# MOSFETadded.net
KiCad netlist of a schematic drawn in EAGLE
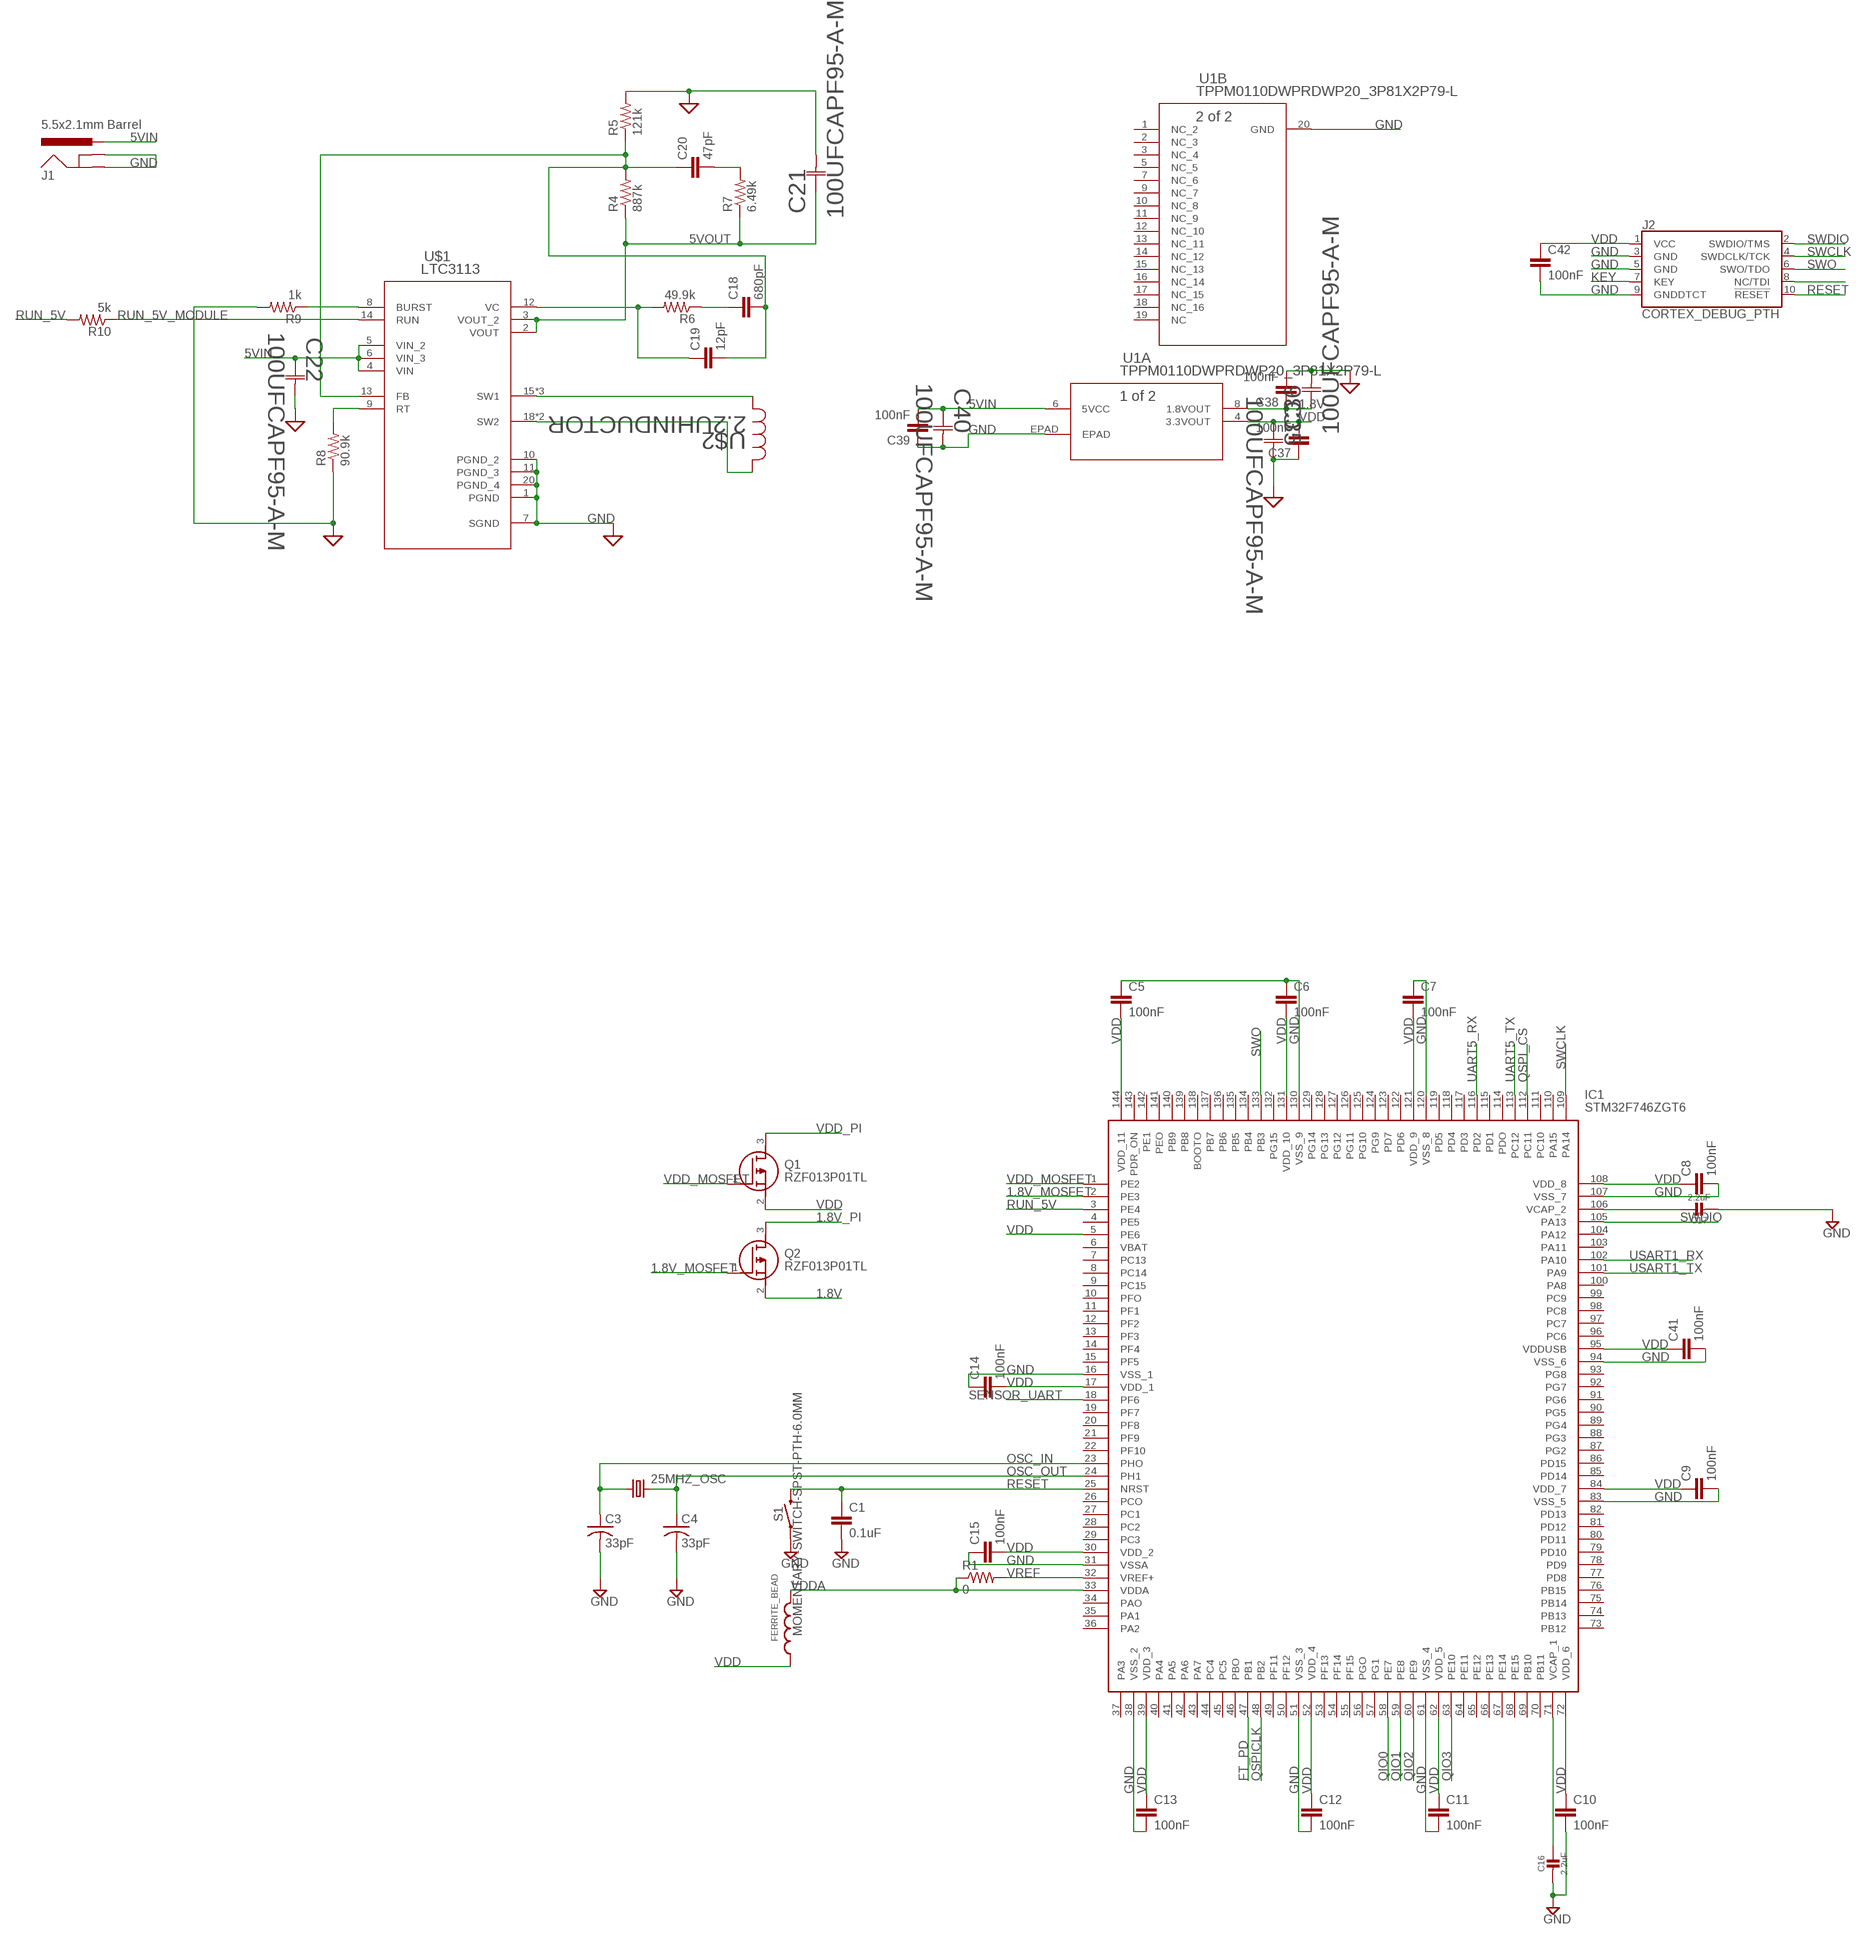
[diagram p0: schematic, sheet 1, part 1 of 2]
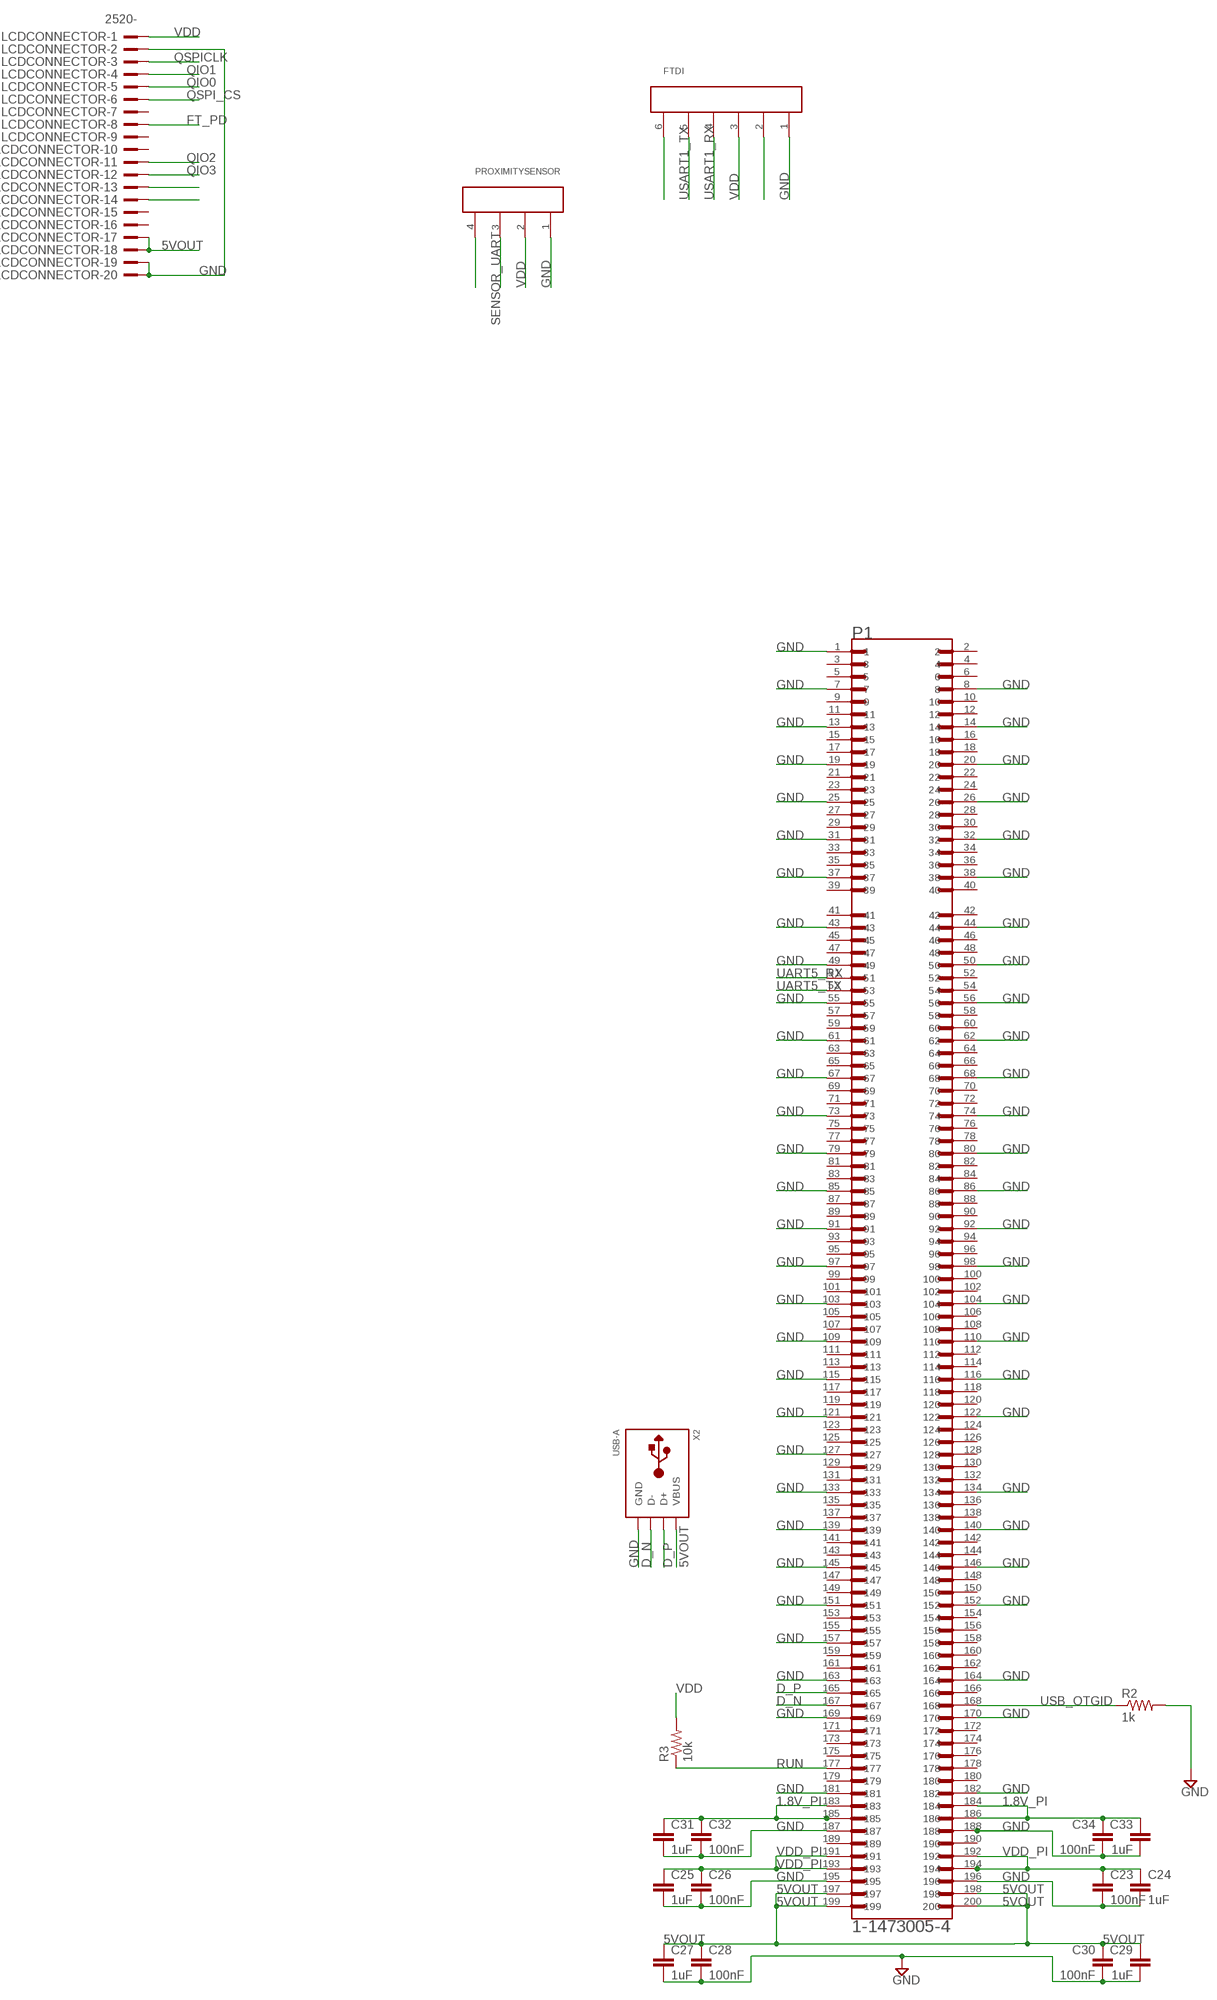
[diagram p1: schematic, sheet 1, part 2 of 2]

(export (version "E")
  (design (tool "Eeschema 10.0.6"))
  (components
    (comp (ref "25MHZ_OSC")
      (value "CRYSTALHC49UP")
      (footprint "eagle-import:HC49UP")
      (libsource (lib "eagle-import") (part "CRYSTALHC49UP"))
    )
    (comp (ref "C1")
      (value "0.1uF")
      (footprint "eagle-import:C0805")
      (libsource (lib "eagle-import") (part "C-EUC0805"))
    )
    (comp (ref "C3")
      (value "33pF")
      (footprint "eagle-import:C0805")
      (libsource (lib "eagle-import") (part "C-USC0805"))
    )
    (comp (ref "C4")
      (value "33pF")
      (footprint "eagle-import:C0805")
      (libsource (lib "eagle-import") (part "C-USC0805"))
    )
    (comp (ref "C5")
      (value "100nF")
      (footprint "eagle-import:C0805")
      (libsource (lib "eagle-import") (part "C-EUC0805"))
    )
    (comp (ref "C6")
      (value "100nF")
      (footprint "eagle-import:C0805")
      (libsource (lib "eagle-import") (part "C-EUC0805"))
    )
    (comp (ref "C7")
      (value "100nF")
      (footprint "eagle-import:C0805")
      (libsource (lib "eagle-import") (part "C-EUC0805"))
    )
    (comp (ref "C8")
      (value "100nF")
      (footprint "eagle-import:C0805")
      (libsource (lib "eagle-import") (part "C-EUC0805"))
    )
    (comp (ref "C9")
      (value "100nF")
      (footprint "eagle-import:C0805")
      (libsource (lib "eagle-import") (part "C-EUC0805"))
    )
    (comp (ref "C10")
      (value "100nF")
      (footprint "eagle-import:C0805")
      (libsource (lib "eagle-import") (part "C-EUC0805"))
    )
    (comp (ref "C11")
      (value "100nF")
      (footprint "eagle-import:C0805")
      (libsource (lib "eagle-import") (part "C-EUC0805"))
    )
    (comp (ref "C12")
      (value "100nF")
      (footprint "eagle-import:C0805")
      (libsource (lib "eagle-import") (part "C-EUC0805"))
    )
    (comp (ref "C13")
      (value "100nF")
      (footprint "eagle-import:C0805")
      (libsource (lib "eagle-import") (part "C-EUC0805"))
    )
    (comp (ref "C14")
      (value "100nF")
      (footprint "eagle-import:C0805")
      (libsource (lib "eagle-import") (part "C-EUC0805"))
    )
    (comp (ref "C15")
      (value "100nF")
      (footprint "eagle-import:C0805")
      (libsource (lib "eagle-import") (part "C-EUC0805"))
    )
    (comp (ref "C16")
      (value "2.2uF")
      (footprint "eagle-import:0805-NO")
      (libsource (lib "eagle-import") (part "CAP_CERAMIC0805-NOOUTLINE"))
    )
    (comp (ref "C17")
      (value "2.2uF")
      (footprint "eagle-import:0805-NO")
      (libsource (lib "eagle-import") (part "CAP_CERAMIC0805-NOOUTLINE"))
    )
    (comp (ref "C18")
      (value "680pF")
      (footprint "eagle-import:C0805")
      (libsource (lib "eagle-import") (part "C-EUC0805"))
    )
    (comp (ref "C19")
      (value "12pF")
      (footprint "eagle-import:C0805")
      (libsource (lib "eagle-import") (part "C-EUC0805"))
    )
    (comp (ref "C20")
      (value "47pF")
      (footprint "eagle-import:C0805")
      (libsource (lib "eagle-import") (part "C-EUC0805"))
    )
    (comp (ref "C21")
      (value "100UFCAPF95-A-M")
      (footprint "eagle-import:F95-A-M")
      (fields (field (name "MANUFACTURER_PART_NUMBER") "F951A107KAAAQ2"))
      (libsource (lib "eagle-import") (part "100UFCAPF95-A-M"))
    )
    (comp (ref "C22")
      (value "100UFCAPF95-A-M")
      (footprint "eagle-import:F95-A-M")
      (fields (field (name "MANUFACTURER_PART_NUMBER") "F951A107KAAAQ2"))
      (libsource (lib "eagle-import") (part "100UFCAPF95-A-M"))
    )
    (comp (ref "C23")
      (value "100nF")
      (footprint "eagle-import:C0805")
      (libsource (lib "eagle-import") (part "C-EUC0805"))
    )
    (comp (ref "C24")
      (value "1uF")
      (footprint "eagle-import:C0805")
      (libsource (lib "eagle-import") (part "C-EUC0805"))
    )
    (comp (ref "C25")
      (value "1uF")
      (footprint "eagle-import:C0805")
      (libsource (lib "eagle-import") (part "C-EUC0805"))
    )
    (comp (ref "C26")
      (value "100nF")
      (footprint "eagle-import:C0805")
      (libsource (lib "eagle-import") (part "C-EUC0805"))
    )
    (comp (ref "C27")
      (value "1uF")
      (footprint "eagle-import:C0805")
      (libsource (lib "eagle-import") (part "C-EUC0805"))
    )
    (comp (ref "C28")
      (value "100nF")
      (footprint "eagle-import:C0805")
      (libsource (lib "eagle-import") (part "C-EUC0805"))
    )
    (comp (ref "C29")
      (value "1uF")
      (footprint "eagle-import:C0805")
      (libsource (lib "eagle-import") (part "C-EUC0805"))
    )
    (comp (ref "C30")
      (value "100nF")
      (footprint "eagle-import:C0805")
      (libsource (lib "eagle-import") (part "C-EUC0805"))
    )
    (comp (ref "C31")
      (value "1uF")
      (footprint "eagle-import:C0805")
      (libsource (lib "eagle-import") (part "C-EUC0805"))
    )
    (comp (ref "C32")
      (value "100nF")
      (footprint "eagle-import:C0805")
      (libsource (lib "eagle-import") (part "C-EUC0805"))
    )
    (comp (ref "C33")
      (value "1uF")
      (footprint "eagle-import:C0805")
      (libsource (lib "eagle-import") (part "C-EUC0805"))
    )
    (comp (ref "C34")
      (value "100nF")
      (footprint "eagle-import:C0805")
      (libsource (lib "eagle-import") (part "C-EUC0805"))
    )
    (comp (ref "C35")
      (value "100UFCAPF95-A-M")
      (footprint "eagle-import:F95-A-M")
      (fields (field (name "MANUFACTURER_PART_NUMBER") "F951A107KAAAQ2"))
      (libsource (lib "eagle-import") (part "100UFCAPF95-A-M"))
    )
    (comp (ref "C36")
      (value "100UFCAPF95-A-M")
      (footprint "eagle-import:F95-A-M")
      (fields (field (name "MANUFACTURER_PART_NUMBER") "F951A107KAAAQ2"))
      (libsource (lib "eagle-import") (part "100UFCAPF95-A-M"))
    )
    (comp (ref "C37")
      (value "100nF")
      (footprint "eagle-import:C0805")
      (libsource (lib "eagle-import") (part "C-EUC0805"))
    )
    (comp (ref "C38")
      (value "100nF")
      (footprint "eagle-import:C0805")
      (libsource (lib "eagle-import") (part "C-EUC0805"))
    )
    (comp (ref "C39")
      (value "100nF")
      (footprint "eagle-import:C0805")
      (libsource (lib "eagle-import") (part "C-EUC0805"))
    )
    (comp (ref "C40")
      (value "100UFCAPF95-A-M")
      (footprint "eagle-import:F95-A-M")
      (fields (field (name "MANUFACTURER_PART_NUMBER") "F951A107KAAAQ2"))
      (libsource (lib "eagle-import") (part "100UFCAPF95-A-M"))
    )
    (comp (ref "C41")
      (value "100nF")
      (footprint "eagle-import:C0805")
      (libsource (lib "eagle-import") (part "C-EUC0805"))
    )
    (comp (ref "C42")
      (value "100nF")
      (footprint "eagle-import:C0805")
      (libsource (lib "eagle-import") (part "C-EUC0805"))
    )
    (comp (ref "FERRITE_BEAD")
      (value "WE-CBA_0805_782853112_HC")
      (footprint "eagle-import:WE-CBA_0805(W=4)")
      (libsource (lib "eagle-import") (part "WE-CBA_0805_HC_782853112"))
    )
    (comp (ref "FTDI")
      (value "66100611622")
      (footprint "eagle-import:66100611622")
      (libsource (lib "eagle-import") (part "66100611622"))
    )
    (comp (ref "IC1")
      (value "STM32F746ZGT6")
      (footprint "eagle-import:QFP50P2200X2200X160-144N")
      (fields
        (field (name "MOUSER_PART_NUMBER") "511-STM32F746ZGT6")
        (field (name "RS_PART_NUMBER") "8820290")
      )
      (libsource (lib "eagle-import") (part "STM32F746ZGT6"))
    )
    (comp (ref "J1")
      (value "5.5x2.1mm Barrel")
      (footprint "eagle-import:POWER_JACK_SMD")
      (libsource (lib "eagle-import") (part "POWER_JACKSMD"))
    )
    (comp (ref "J2")
      (value "CORTEX_DEBUG_PTH")
      (footprint "eagle-import:2X5-PTH-1.27MM")
      (libsource (lib "eagle-import") (part "CORTEX_DEBUG_PTH"))
    )
    (comp (ref "LCDCONNECTOR")
      (value "2520-")
      (footprint "eagle-import:PAK100_2500-20")
      (libsource (lib "eagle-import") (part "2520-"))
    )
    (comp (ref "P1")
      (value "1-1473005-4")
      (footprint "eagle-import:TE_1-1473005-4")
      (fields (field (name "MF") "TE Connectivity"))
      (libsource (lib "eagle-import") (part "1-1473005-4"))
    )
    (comp (ref "PROXIMITYSENSOR")
      (value "66100411622")
      (footprint "eagle-import:66100411622")
      (libsource (lib "eagle-import") (part "66100411622"))
    )
    (comp (ref "Q1")
      (value "RZF013P01TL")
      (footprint "eagle-import:SOT65P210X85-3N")
      (fields (field (name "MOUSER_PART_NUMBER") "755-RZF013P01TL"))
      (libsource (lib "eagle-import") (part "RZF013P01TL"))
    )
    (comp (ref "Q2")
      (value "RZF013P01TL")
      (footprint "eagle-import:SOT65P210X85-3N")
      (fields (field (name "MOUSER_PART_NUMBER") "755-RZF013P01TL"))
      (libsource (lib "eagle-import") (part "RZF013P01TL"))
    )
    (comp (ref "R1")
      (value "0")
      (footprint "eagle-import:R0805")
      (libsource (lib "eagle-import") (part "R-US_R0805"))
    )
    (comp (ref "R2")
      (value "1k")
      (footprint "eagle-import:R0805")
      (libsource (lib "eagle-import") (part "R-US_R0805"))
    )
    (comp (ref "R3")
      (value "10k")
      (footprint "eagle-import:R0805")
      (libsource (lib "eagle-import") (part "R-US_R0805"))
    )
    (comp (ref "R4")
      (value "887k")
      (footprint "eagle-import:R0805")
      (libsource (lib "eagle-import") (part "resistor_348_R-US_R0805"))
    )
    (comp (ref "R5")
      (value "121k")
      (footprint "eagle-import:R0805")
      (libsource (lib "eagle-import") (part "resistor_348_R-US_R0805"))
    )
    (comp (ref "R6")
      (value "49.9k")
      (footprint "eagle-import:R0805")
      (libsource (lib "eagle-import") (part "resistor_348_R-US_R0805"))
    )
    (comp (ref "R7")
      (value "6.49k")
      (footprint "eagle-import:R0805")
      (libsource (lib "eagle-import") (part "resistor_348_R-US_R0805"))
    )
    (comp (ref "R8")
      (value "90.9k")
      (footprint "eagle-import:R0805")
      (libsource (lib "eagle-import") (part "resistor_348_R-US_R0805"))
    )
    (comp (ref "R9")
      (value "1k")
      (footprint "eagle-import:R0805")
      (libsource (lib "eagle-import") (part "resistor_348_R-US_R0805"))
    )
    (comp (ref "R10")
      (value "5k")
      (footprint "eagle-import:R0805")
      (libsource (lib "eagle-import") (part "resistor_348_R-US_R0805"))
    )
    (comp (ref "S1")
      (value "MOMENTARY-SWITCH-SPST-PTH-6.0MM")
      (footprint "eagle-import:TACTILE_SWITCH_PTH_6.0MM")
      (libsource (lib "eagle-import") (part "MOMENTARY-SWITCH-SPST-PTH-6.0MM"))
    )
    (comp (ref "U$1")
      (value "LTC3113")
      (footprint "eagle-import:TSSOP-20_FE_CA")
      (libsource (lib "eagle-import") (part "LTC3113"))
    )
    (comp (ref "U$2")
      (value "2.2UHINDUCTOR")
      (footprint "eagle-import:IND_10040")
      (libsource (lib "eagle-import") (part "2.2UHINDUCTOR"))
    )
    (comp (ref "U1")
      (value "TPPM0110DWPRDWP20_3P81X2P79-L")
      (footprint "eagle-import:DWP20_3P81X2P79-L")
      (fields (field (name "MANUFACTURER_PART_NUMBER") "TPPM0110DWPR"))
      (libsource (lib "eagle-import") (part "TPPM0110DWPRDWP20_3P81X2P79-L"))
    )
    (comp (ref "X2")
      (value "USB-A")
      (footprint "eagle-import:MOLEX_480371000")
      (libsource (lib "eagle-import") (part "USB-A"))
    )
  )
  (nets
    (net (code "1") (name "/1.8V") (class "Default")
      (node (ref "C36") (pin "1") (pinfunction "1_1") (pintype "passive"))
      (node (ref "C38") (pin "1") (pinfunction "1_1") (pintype "passive"))
      (node (ref "Q2") (pin "2") (pinfunction "S_2") (pintype "bidirectional"))
      (node (ref "U1") (pin "8") (pinfunction "1.8VOUT_8") (pintype "output"))
    )
    (net (code "2") (name "/1.8V_MOSFET") (class "Default")
      (node (ref "IC1") (pin "2") (pinfunction "PE3_2") (pintype "bidirectional"))
      (node (ref "Q2") (pin "1") (pinfunction "G_1") (pintype "bidirectional"))
    )
    (net (code "3") (name "/1.8V_PI") (class "Default")
      (node (ref "C31") (pin "1") (pinfunction "1_1") (pintype "passive"))
      (node (ref "C32") (pin "1") (pinfunction "1_1") (pintype "passive"))
      (node (ref "C33") (pin "1") (pinfunction "1_1") (pintype "passive"))
      (node (ref "C34") (pin "1") (pinfunction "1_1") (pintype "passive"))
      (node (ref "P1") (pin "183") (pinfunction "183_183") (pintype "passive"))
      (node (ref "P1") (pin "184") (pinfunction "184_184") (pintype "passive"))
      (node (ref "P1") (pin "185") (pinfunction "185_185") (pintype "passive"))
      (node (ref "P1") (pin "186") (pinfunction "186_186") (pintype "passive"))
      (node (ref "Q2") (pin "3") (pinfunction "D_3") (pintype "bidirectional"))
    )
    (net (code "4") (name "/5VIN") (class "Default")
      (node (ref "C22") (pin "1") (pinfunction "1_1") (pintype "passive"))
      (node (ref "C39") (pin "2") (pinfunction "2_2") (pintype "passive"))
      (node (ref "C40") (pin "1") (pinfunction "1_1") (pintype "passive"))
      (node (ref "J1") (pin "VIN0") (pinfunction "PWR_VIN0") (pintype "bidirectional"))
      (node (ref "U$1") (pin "4") (pinfunction "VIN_4") (pintype "passive"))
      (node (ref "U$1") (pin "5") (pinfunction "VIN_2_5") (pintype "passive"))
      (node (ref "U$1") (pin "6") (pinfunction "VIN_3_6") (pintype "passive"))
      (node (ref "U1") (pin "6") (pinfunction "5VCC_6") (pintype "input"))
    )
    (net (code "5") (name "/5VOUT") (class "Default")
      (node (ref "C21") (pin "1") (pinfunction "1_1") (pintype "passive"))
      (node (ref "C27") (pin "1") (pinfunction "1_1") (pintype "passive"))
      (node (ref "C28") (pin "1") (pinfunction "1_1") (pintype "passive"))
      (node (ref "C29") (pin "1") (pinfunction "1_1") (pintype "passive"))
      (node (ref "C30") (pin "1") (pinfunction "1_1") (pintype "passive"))
      (node (ref "LCDCONNECTOR") (pin "17") (pinfunction "KL_17") (pintype "passive"))
      (node (ref "LCDCONNECTOR") (pin "18") (pinfunction "KL_18") (pintype "passive"))
      (node (ref "P1") (pin "197") (pinfunction "197_197") (pintype "passive"))
      (node (ref "P1") (pin "198") (pinfunction "198_198") (pintype "passive"))
      (node (ref "P1") (pin "199") (pinfunction "199_199") (pintype "passive"))
      (node (ref "P1") (pin "200") (pinfunction "200_200") (pintype "passive"))
      (node (ref "R4") (pin "1") (pinfunction "1_1") (pintype "passive"))
      (node (ref "R7") (pin "1") (pinfunction "1_1") (pintype "passive"))
      (node (ref "U$1") (pin "2") (pinfunction "VOUT_2") (pintype "passive"))
      (node (ref "U$1") (pin "3") (pinfunction "VOUT_2_3") (pintype "passive"))
      (node (ref "X2") (pin "1") (pinfunction "VBUS_1") (pintype "power_in"))
    )
    (net (code "6") (name "/D_N") (class "Default")
      (node (ref "P1") (pin "167") (pinfunction "167_167") (pintype "passive"))
      (node (ref "X2") (pin "2") (pinfunction "D-_2") (pintype "bidirectional"))
    )
    (net (code "7") (name "/D_P") (class "Default")
      (node (ref "P1") (pin "165") (pinfunction "165_165") (pintype "passive"))
      (node (ref "X2") (pin "3") (pinfunction "D+_3") (pintype "bidirectional"))
    )
    (net (code "8") (name "/FT_PD") (class "Default")
      (node (ref "IC1") (pin "47") (pinfunction "PB1_47") (pintype "bidirectional"))
      (node (ref "LCDCONNECTOR") (pin "8") (pinfunction "KL_8") (pintype "passive"))
    )
    (net (code "9") (name "/KEY") (class "Default")
      (node (ref "J2") (pin "7") (pinfunction "KEY_7") (pintype "bidirectional"))
    )
    (net (code "10") (name "/OSC_IN") (class "Default")
      (node (ref "25MHZ_OSC") (pin "1") (pinfunction "1_1") (pintype "passive"))
      (node (ref "C3") (pin "1") (pinfunction "1_1") (pintype "passive"))
      (node (ref "IC1") (pin "23") (pinfunction "PHO_23") (pintype "bidirectional"))
    )
    (net (code "11") (name "/OSC_OUT") (class "Default")
      (node (ref "25MHZ_OSC") (pin "2") (pinfunction "2_2") (pintype "passive"))
      (node (ref "C4") (pin "1") (pinfunction "1_1") (pintype "passive"))
      (node (ref "IC1") (pin "24") (pinfunction "PH1_24") (pintype "bidirectional"))
    )
    (net (code "12") (name "/QIO0") (class "Default")
      (node (ref "IC1") (pin "58") (pinfunction "PE7_58") (pintype "bidirectional"))
      (node (ref "LCDCONNECTOR") (pin "5") (pinfunction "KL_5") (pintype "passive"))
    )
    (net (code "13") (name "/QIO1") (class "Default")
      (node (ref "IC1") (pin "59") (pinfunction "PE8_59") (pintype "bidirectional"))
      (node (ref "LCDCONNECTOR") (pin "4") (pinfunction "KL_4") (pintype "passive"))
    )
    (net (code "14") (name "/QIO2") (class "Default")
      (node (ref "IC1") (pin "60") (pinfunction "PE9_60") (pintype "bidirectional"))
      (node (ref "LCDCONNECTOR") (pin "11") (pinfunction "KL_11") (pintype "passive"))
    )
    (net (code "15") (name "/QIO3") (class "Default")
      (node (ref "IC1") (pin "63") (pinfunction "PE10_63") (pintype "bidirectional"))
      (node (ref "LCDCONNECTOR") (pin "12") (pinfunction "KL_12") (pintype "passive"))
    )
    (net (code "16") (name "/QSPICLK") (class "Default")
      (node (ref "IC1") (pin "48") (pinfunction "PB2_48") (pintype "bidirectional"))
      (node (ref "LCDCONNECTOR") (pin "3") (pinfunction "KL_3") (pintype "passive"))
    )
    (net (code "17") (name "/QSPI_CS") (class "Default")
      (node (ref "IC1") (pin "112") (pinfunction "PC11_112") (pintype "bidirectional"))
      (node (ref "LCDCONNECTOR") (pin "6") (pinfunction "KL_6") (pintype "passive"))
    )
    (net (code "18") (name "/RESET") (class "Default")
      (node (ref "C1") (pin "1") (pinfunction "1_1") (pintype "passive"))
      (node (ref "IC1") (pin "25") (pinfunction "NRST_25") (pintype "input"))
      (node (ref "J2") (pin "10") (pinfunction "~{RESET}_10") (pintype "bidirectional"))
      (node (ref "S1") (pin "3") (pinfunction "2_3") (pintype "passive"))
    )
    (net (code "19") (name "/RUN") (class "Default")
      (node (ref "P1") (pin "177") (pinfunction "177_177") (pintype "passive"))
      (node (ref "R3") (pin "1") (pinfunction "1_1") (pintype "passive"))
    )
    (net (code "20") (name "/RUN_5V") (class "Default")
      (node (ref "IC1") (pin "3") (pinfunction "PE4_3") (pintype "bidirectional"))
      (node (ref "R10") (pin "2") (pinfunction "2_2") (pintype "passive"))
    )
    (net (code "21") (name "/RUN_5V_MODULE") (class "Default")
      (node (ref "R10") (pin "1") (pinfunction "1_1") (pintype "passive"))
      (node (ref "U$1") (pin "14") (pinfunction "RUN_14") (pintype "passive"))
    )
    (net (code "22") (name "/SENSOR_UART") (class "Default")
      (node (ref "IC1") (pin "18") (pinfunction "PF6_18") (pintype "bidirectional"))
      (node (ref "PROXIMITYSENSOR") (pin "3") (pinfunction "3_3") (pintype "passive"))
    )
    (net (code "23") (name "/SWCLK") (class "Default")
      (node (ref "IC1") (pin "109") (pinfunction "PA14_109") (pintype "bidirectional"))
      (node (ref "J2") (pin "4") (pinfunction "SWDCLK/TCK_4") (pintype "bidirectional"))
    )
    (net (code "24") (name "/SWDIO") (class "Default")
      (node (ref "IC1") (pin "105") (pinfunction "PA13_105") (pintype "bidirectional"))
      (node (ref "J2") (pin "2") (pinfunction "SWDIO/TMS_2") (pintype "bidirectional"))
    )
    (net (code "25") (name "/SWO") (class "Default")
      (node (ref "IC1") (pin "133") (pinfunction "PB3_133") (pintype "bidirectional"))
      (node (ref "J2") (pin "6") (pinfunction "SWO/TDO_6") (pintype "bidirectional"))
    )
    (net (code "26") (name "/UART5_RX") (class "Default")
      (node (ref "IC1") (pin "116") (pinfunction "PD2_116") (pintype "bidirectional"))
      (node (ref "P1") (pin "51") (pinfunction "51_51") (pintype "passive"))
    )
    (net (code "27") (name "/UART5_TX") (class "Default")
      (node (ref "IC1") (pin "113") (pinfunction "PC12_113") (pintype "bidirectional"))
      (node (ref "P1") (pin "53") (pinfunction "53_53") (pintype "passive"))
    )
    (net (code "28") (name "/USART1_RX") (class "Default")
      (node (ref "FTDI") (pin "4") (pinfunction "4_4") (pintype "passive"))
      (node (ref "IC1") (pin "102") (pinfunction "PA10_102") (pintype "bidirectional"))
    )
    (net (code "29") (name "/USART1_TX") (class "Default")
      (node (ref "FTDI") (pin "5") (pinfunction "5_5") (pintype "passive"))
      (node (ref "IC1") (pin "101") (pinfunction "PA9_101") (pintype "bidirectional"))
    )
    (net (code "30") (name "/USB_OTGID") (class "Default")
      (node (ref "P1") (pin "168") (pinfunction "168_168") (pintype "passive"))
      (node (ref "R2") (pin "1") (pinfunction "1_1") (pintype "passive"))
    )
    (net (code "31") (name "/VDD") (class "Default")
      (node (ref "C10") (pin "1") (pinfunction "1_1") (pintype "passive"))
      (node (ref "C11") (pin "1") (pinfunction "1_1") (pintype "passive"))
      (node (ref "C12") (pin "1") (pinfunction "1_1") (pintype "passive"))
      (node (ref "C13") (pin "1") (pinfunction "1_1") (pintype "passive"))
      (node (ref "C14") (pin "2") (pinfunction "2_2") (pintype "passive"))
      (node (ref "C15") (pin "2") (pinfunction "2_2") (pintype "passive"))
      (node (ref "C35") (pin "1") (pinfunction "1_1") (pintype "passive"))
      (node (ref "C37") (pin "2") (pinfunction "2_2") (pintype "passive"))
      (node (ref "C41") (pin "1") (pinfunction "1_1") (pintype "passive"))
      (node (ref "C42") (pin "1") (pinfunction "1_1") (pintype "passive"))
      (node (ref "C5") (pin "2") (pinfunction "2_2") (pintype "passive"))
      (node (ref "C6") (pin "2") (pinfunction "2_2") (pintype "passive"))
      (node (ref "C7") (pin "2") (pinfunction "2_2") (pintype "passive"))
      (node (ref "C8") (pin "1") (pinfunction "1_1") (pintype "passive"))
      (node (ref "C9") (pin "1") (pinfunction "1_1") (pintype "passive"))
      (node (ref "FERRITE_BEAD") (pin "1") (pinfunction "1_1") (pintype "passive"))
      (node (ref "FTDI") (pin "3") (pinfunction "3_3") (pintype "passive"))
      (node (ref "IC1") (pin "108") (pinfunction "VDD_8_108") (pintype "power_in"))
      (node (ref "IC1") (pin "121") (pinfunction "VDD_9_121") (pintype "power_in"))
      (node (ref "IC1") (pin "131") (pinfunction "VDD_10_131") (pintype "power_in"))
      (node (ref "IC1") (pin "144") (pinfunction "VDD_11_144") (pintype "power_in"))
      (node (ref "IC1") (pin "17") (pinfunction "VDD_1_17") (pintype "power_in"))
      (node (ref "IC1") (pin "30") (pinfunction "VDD_2_30") (pintype "power_in"))
      (node (ref "IC1") (pin "39") (pinfunction "VDD_3_39") (pintype "power_in"))
      (node (ref "IC1") (pin "5") (pinfunction "PE6_5") (pintype "bidirectional"))
      (node (ref "IC1") (pin "52") (pinfunction "VDD_4_52") (pintype "power_in"))
      (node (ref "IC1") (pin "62") (pinfunction "VDD_5_62") (pintype "power_in"))
      (node (ref "IC1") (pin "72") (pinfunction "VDD_6_72") (pintype "power_in"))
      (node (ref "IC1") (pin "84") (pinfunction "VDD_7_84") (pintype "power_in"))
      (node (ref "IC1") (pin "95") (pinfunction "VDDUSB_95") (pintype "power_in"))
      (node (ref "J2") (pin "1") (pinfunction "VCC_1") (pintype "bidirectional"))
      (node (ref "LCDCONNECTOR") (pin "1") (pinfunction "KL_1") (pintype "passive"))
      (node (ref "PROXIMITYSENSOR") (pin "2") (pinfunction "2_2") (pintype "passive"))
      (node (ref "Q1") (pin "2") (pinfunction "S_2") (pintype "bidirectional"))
      (node (ref "R3") (pin "2") (pinfunction "2_2") (pintype "passive"))
      (node (ref "U1") (pin "4") (pinfunction "3.3VOUT_4") (pintype "output"))
    )
    (net (code "32") (name "/VDDA") (class "Default")
      (node (ref "FERRITE_BEAD") (pin "2") (pinfunction "2_2") (pintype "passive"))
      (node (ref "IC1") (pin "33") (pinfunction "VDDA_33") (pintype "power_in"))
      (node (ref "R1") (pin "1") (pinfunction "1_1") (pintype "passive"))
    )
    (net (code "33") (name "/VDD_MOSFET") (class "Default")
      (node (ref "IC1") (pin "1") (pinfunction "PE2_1") (pintype "bidirectional"))
      (node (ref "Q1") (pin "1") (pinfunction "G_1") (pintype "bidirectional"))
    )
    (net (code "34") (name "/VDD_PI") (class "Default")
      (node (ref "C23") (pin "1") (pinfunction "1_1") (pintype "passive"))
      (node (ref "C24") (pin "1") (pinfunction "1_1") (pintype "passive"))
      (node (ref "C25") (pin "1") (pinfunction "1_1") (pintype "passive"))
      (node (ref "C26") (pin "1") (pinfunction "1_1") (pintype "passive"))
      (node (ref "P1") (pin "191") (pinfunction "191_191") (pintype "passive"))
      (node (ref "P1") (pin "192") (pinfunction "192_192") (pintype "passive"))
      (node (ref "P1") (pin "193") (pinfunction "193_193") (pintype "passive"))
      (node (ref "P1") (pin "194") (pinfunction "194_194") (pintype "passive"))
      (node (ref "Q1") (pin "3") (pinfunction "D_3") (pintype "bidirectional"))
    )
    (net (code "35") (name "/VREF") (class "Default")
      (node (ref "IC1") (pin "32") (pinfunction "VREF+_32") (pintype "input"))
      (node (ref "R1") (pin "2") (pinfunction "2_2") (pintype "passive"))
    )
    (net (code "36") (name "GND") (class "Default")
      (node (ref "C1") (pin "2") (pinfunction "2_2") (pintype "passive"))
      (node (ref "C10") (pin "2") (pinfunction "2_2") (pintype "passive"))
      (node (ref "C11") (pin "2") (pinfunction "2_2") (pintype "passive"))
      (node (ref "C12") (pin "2") (pinfunction "2_2") (pintype "passive"))
      (node (ref "C13") (pin "2") (pinfunction "2_2") (pintype "passive"))
      (node (ref "C14") (pin "1") (pinfunction "1_1") (pintype "passive"))
      (node (ref "C15") (pin "1") (pinfunction "1_1") (pintype "passive"))
      (node (ref "C16") (pin "2") (pinfunction "2_2") (pintype "passive"))
      (node (ref "C17") (pin "2") (pinfunction "2_2") (pintype "passive"))
      (node (ref "C21") (pin "2") (pinfunction "2_2") (pintype "passive"))
      (node (ref "C22") (pin "2") (pinfunction "2_2") (pintype "passive"))
      (node (ref "C23") (pin "2") (pinfunction "2_2") (pintype "passive"))
      (node (ref "C24") (pin "2") (pinfunction "2_2") (pintype "passive"))
      (node (ref "C25") (pin "2") (pinfunction "2_2") (pintype "passive"))
      (node (ref "C26") (pin "2") (pinfunction "2_2") (pintype "passive"))
      (node (ref "C27") (pin "2") (pinfunction "2_2") (pintype "passive"))
      (node (ref "C28") (pin "2") (pinfunction "2_2") (pintype "passive"))
      (node (ref "C29") (pin "2") (pinfunction "2_2") (pintype "passive"))
      (node (ref "C3") (pin "2") (pinfunction "2_2") (pintype "passive"))
      (node (ref "C30") (pin "2") (pinfunction "2_2") (pintype "passive"))
      (node (ref "C31") (pin "2") (pinfunction "2_2") (pintype "passive"))
      (node (ref "C32") (pin "2") (pinfunction "2_2") (pintype "passive"))
      (node (ref "C33") (pin "2") (pinfunction "2_2") (pintype "passive"))
      (node (ref "C34") (pin "2") (pinfunction "2_2") (pintype "passive"))
      (node (ref "C35") (pin "2") (pinfunction "2_2") (pintype "passive"))
      (node (ref "C36") (pin "2") (pinfunction "2_2") (pintype "passive"))
      (node (ref "C37") (pin "1") (pinfunction "1_1") (pintype "passive"))
      (node (ref "C38") (pin "2") (pinfunction "2_2") (pintype "passive"))
      (node (ref "C39") (pin "1") (pinfunction "1_1") (pintype "passive"))
      (node (ref "C4") (pin "2") (pinfunction "2_2") (pintype "passive"))
      (node (ref "C40") (pin "2") (pinfunction "2_2") (pintype "passive"))
      (node (ref "C41") (pin "2") (pinfunction "2_2") (pintype "passive"))
      (node (ref "C42") (pin "2") (pinfunction "2_2") (pintype "passive"))
      (node (ref "C5") (pin "1") (pinfunction "1_1") (pintype "passive"))
      (node (ref "C6") (pin "1") (pinfunction "1_1") (pintype "passive"))
      (node (ref "C7") (pin "1") (pinfunction "1_1") (pintype "passive"))
      (node (ref "C8") (pin "2") (pinfunction "2_2") (pintype "passive"))
      (node (ref "C9") (pin "2") (pinfunction "2_2") (pintype "passive"))
      (node (ref "FTDI") (pin "1") (pinfunction "1_1") (pintype "passive"))
      (node (ref "IC1") (pin "107") (pinfunction "VSS_7_107") (pintype "power_in"))
      (node (ref "IC1") (pin "120") (pinfunction "VSS_8_120") (pintype "power_in"))
      (node (ref "IC1") (pin "130") (pinfunction "VSS_9_130") (pintype "power_in"))
      (node (ref "IC1") (pin "16") (pinfunction "VSS_1_16") (pintype "power_in"))
      (node (ref "IC1") (pin "31") (pinfunction "VSSA_31") (pintype "power_in"))
      (node (ref "IC1") (pin "38") (pinfunction "VSS_2_38") (pintype "power_in"))
      (node (ref "IC1") (pin "51") (pinfunction "VSS_3_51") (pintype "power_in"))
      (node (ref "IC1") (pin "61") (pinfunction "VSS_4_61") (pintype "power_in"))
      (node (ref "IC1") (pin "83") (pinfunction "VSS_5_83") (pintype "power_in"))
      (node (ref "IC1") (pin "94") (pinfunction "VSS_6_94") (pintype "power_in"))
      (node (ref "J1") (pin "GND") (pinfunction "GNDBREAK_GND") (pintype "bidirectional"))
      (node (ref "J1") (pin "P$4") (pinfunction "GND_P$4") (pintype "bidirectional"))
      (node (ref "J2") (pin "3") (pinfunction "GND_3") (pintype "bidirectional"))
      (node (ref "J2") (pin "5") (pinfunction "GND_5") (pintype "bidirectional"))
      (node (ref "J2") (pin "9") (pinfunction "GNDDTCT_9") (pintype "bidirectional"))
      (node (ref "LCDCONNECTOR") (pin "19") (pinfunction "KL_19") (pintype "passive"))
      (node (ref "LCDCONNECTOR") (pin "2") (pinfunction "KL_2") (pintype "passive"))
      (node (ref "LCDCONNECTOR") (pin "20") (pinfunction "KL_20") (pintype "passive"))
      (node (ref "P1") (pin "1") (pinfunction "1_1") (pintype "passive"))
      (node (ref "P1") (pin "103") (pinfunction "103_103") (pintype "passive"))
      (node (ref "P1") (pin "104") (pinfunction "104_104") (pintype "passive"))
      (node (ref "P1") (pin "109") (pinfunction "109_109") (pintype "passive"))
      (node (ref "P1") (pin "110") (pinfunction "110_110") (pintype "passive"))
      (node (ref "P1") (pin "115") (pinfunction "115_115") (pintype "passive"))
      (node (ref "P1") (pin "116") (pinfunction "116_116") (pintype "passive"))
      (node (ref "P1") (pin "121") (pinfunction "121_121") (pintype "passive"))
      (node (ref "P1") (pin "122") (pinfunction "122_122") (pintype "passive"))
      (node (ref "P1") (pin "127") (pinfunction "127_127") (pintype "passive"))
      (node (ref "P1") (pin "13") (pinfunction "13_13") (pintype "passive"))
      (node (ref "P1") (pin "133") (pinfunction "133_133") (pintype "passive"))
      (node (ref "P1") (pin "134") (pinfunction "134_134") (pintype "passive"))
      (node (ref "P1") (pin "139") (pinfunction "139_139") (pintype "passive"))
      (node (ref "P1") (pin "14") (pinfunction "14_14") (pintype "passive"))
      (node (ref "P1") (pin "140") (pinfunction "140_140") (pintype "passive"))
      (node (ref "P1") (pin "145") (pinfunction "145_145") (pintype "passive"))
      (node (ref "P1") (pin "146") (pinfunction "146_146") (pintype "passive"))
      (node (ref "P1") (pin "151") (pinfunction "151_151") (pintype "passive"))
      (node (ref "P1") (pin "152") (pinfunction "152_152") (pintype "passive"))
      (node (ref "P1") (pin "157") (pinfunction "157_157") (pintype "passive"))
      (node (ref "P1") (pin "163") (pinfunction "163_163") (pintype "passive"))
      (node (ref "P1") (pin "164") (pinfunction "164_164") (pintype "passive"))
      (node (ref "P1") (pin "169") (pinfunction "169_169") (pintype "passive"))
      (node (ref "P1") (pin "170") (pinfunction "170_170") (pintype "passive"))
      (node (ref "P1") (pin "181") (pinfunction "181_181") (pintype "passive"))
      (node (ref "P1") (pin "182") (pinfunction "182_182") (pintype "passive"))
      (node (ref "P1") (pin "187") (pinfunction "187_187") (pintype "passive"))
      (node (ref "P1") (pin "188") (pinfunction "188_188") (pintype "passive"))
      (node (ref "P1") (pin "19") (pinfunction "19_19") (pintype "passive"))
      (node (ref "P1") (pin "195") (pinfunction "195_195") (pintype "passive"))
      (node (ref "P1") (pin "196") (pinfunction "196_196") (pintype "passive"))
      (node (ref "P1") (pin "20") (pinfunction "20_20") (pintype "passive"))
      (node (ref "P1") (pin "25") (pinfunction "25_25") (pintype "passive"))
      (node (ref "P1") (pin "26") (pinfunction "26_26") (pintype "passive"))
      (node (ref "P1") (pin "31") (pinfunction "31_31") (pintype "passive"))
      (node (ref "P1") (pin "32") (pinfunction "32_32") (pintype "passive"))
      (node (ref "P1") (pin "37") (pinfunction "37_37") (pintype "passive"))
      (node (ref "P1") (pin "38") (pinfunction "38_38") (pintype "passive"))
      (node (ref "P1") (pin "43") (pinfunction "43_43") (pintype "passive"))
      (node (ref "P1") (pin "44") (pinfunction "44_44") (pintype "passive"))
      (node (ref "P1") (pin "49") (pinfunction "49_49") (pintype "passive"))
      (node (ref "P1") (pin "50") (pinfunction "50_50") (pintype "passive"))
      (node (ref "P1") (pin "55") (pinfunction "55_55") (pintype "passive"))
      (node (ref "P1") (pin "56") (pinfunction "56_56") (pintype "passive"))
      (node (ref "P1") (pin "61") (pinfunction "61_61") (pintype "passive"))
      (node (ref "P1") (pin "62") (pinfunction "62_62") (pintype "passive"))
      (node (ref "P1") (pin "67") (pinfunction "67_67") (pintype "passive"))
      (node (ref "P1") (pin "68") (pinfunction "68_68") (pintype "passive"))
      (node (ref "P1") (pin "7") (pinfunction "7_7") (pintype "passive"))
      (node (ref "P1") (pin "73") (pinfunction "73_73") (pintype "passive"))
      (node (ref "P1") (pin "74") (pinfunction "74_74") (pintype "passive"))
      (node (ref "P1") (pin "79") (pinfunction "79_79") (pintype "passive"))
      (node (ref "P1") (pin "8") (pinfunction "8_8") (pintype "passive"))
      (node (ref "P1") (pin "80") (pinfunction "80_80") (pintype "passive"))
      (node (ref "P1") (pin "85") (pinfunction "85_85") (pintype "passive"))
      (node (ref "P1") (pin "86") (pinfunction "86_86") (pintype "passive"))
      (node (ref "P1") (pin "91") (pinfunction "91_91") (pintype "passive"))
      (node (ref "P1") (pin "92") (pinfunction "92_92") (pintype "passive"))
      (node (ref "P1") (pin "97") (pinfunction "97_97") (pintype "passive"))
      (node (ref "P1") (pin "98") (pinfunction "98_98") (pintype "passive"))
      (node (ref "PROXIMITYSENSOR") (pin "1") (pinfunction "1_1") (pintype "passive"))
      (node (ref "R2") (pin "2") (pinfunction "2_2") (pintype "passive"))
      (node (ref "R5") (pin "2") (pinfunction "2_2") (pintype "passive"))
      (node (ref "R8") (pin "1") (pinfunction "1_1") (pintype "passive"))
      (node (ref "R9") (pin "2") (pinfunction "2_2") (pintype "passive"))
      (node (ref "S1") (pin "1") (pinfunction "1_1") (pintype "passive"))
      (node (ref "U$1") (pin "1") (pinfunction "PGND_1") (pintype "passive"))
      (node (ref "U$1") (pin "10") (pinfunction "PGND_2_10") (pintype "passive"))
      (node (ref "U$1") (pin "11") (pinfunction "PGND_3_11") (pintype "passive"))
      (node (ref "U$1") (pin "20") (pinfunction "PGND_4_20") (pintype "passive"))
      (node (ref "U$1") (pin "7") (pinfunction "SGND_7") (pintype "passive"))
      (node (ref "U1") (pin "20") (pinfunction "GND_20") (pintype "power_in"))
      (node (ref "U1") (pin "EPAD") (pinfunction "EPAD_EPAD") (pintype "passive"))
      (node (ref "X2") (pin "4") (pinfunction "GND_4") (pintype "power_in"))
    )
    (net (code "37") (name "Net-(C18-Pad1)") (class "Default")
      (node (ref "C18") (pin "1") (pinfunction "1_1") (pintype "passive"))
      (node (ref "R6") (pin "1") (pinfunction "1_1") (pintype "passive"))
    )
    (net (code "38") (name "Net-(C20-Pad2)") (class "Default")
      (node (ref "C20") (pin "2") (pinfunction "2_2") (pintype "passive"))
      (node (ref "R7") (pin "2") (pinfunction "2_2") (pintype "passive"))
    )
    (net (code "39") (name "Net-(IC1-VCAP_1)") (class "Default")
      (node (ref "C16") (pin "1") (pinfunction "1_1") (pintype "passive"))
      (node (ref "IC1") (pin "71") (pinfunction "VCAP_1_71") (pintype "bidirectional"))
    )
    (net (code "40") (name "Net-(IC1-VCAP_2)") (class "Default")
      (node (ref "C17") (pin "1") (pinfunction "1_1") (pintype "passive"))
      (node (ref "IC1") (pin "106") (pinfunction "VCAP_2_106") (pintype "bidirectional"))
    )
    (net (code "41") (name "Net-(U$1-BURST)") (class "Default")
      (node (ref "R9") (pin "1") (pinfunction "1_1") (pintype "passive"))
      (node (ref "U$1") (pin "8") (pinfunction "BURST_8") (pintype "passive"))
    )
    (net (code "42") (name "Net-(U$1-FB)") (class "Default")
      (node (ref "C18") (pin "2") (pinfunction "2_2") (pintype "passive"))
      (node (ref "C19") (pin "2") (pinfunction "2_2") (pintype "passive"))
      (node (ref "C20") (pin "1") (pinfunction "1_1") (pintype "passive"))
      (node (ref "R4") (pin "2") (pinfunction "2_2") (pintype "passive"))
      (node (ref "R5") (pin "1") (pinfunction "1_1") (pintype "passive"))
      (node (ref "U$1") (pin "13") (pinfunction "FB_13") (pintype "passive"))
    )
    (net (code "43") (name "Net-(U$1-RT)") (class "Default")
      (node (ref "R8") (pin "2") (pinfunction "2_2") (pintype "passive"))
      (node (ref "U$1") (pin "9") (pinfunction "RT_9") (pintype "passive"))
    )
    (net (code "44") (name "Net-(U$1-SW1-Pad15)") (class "Default")
      (node (ref "U$1") (pin "15") (pinfunction "SW1_15") (pintype "passive"))
      (node (ref "U$1") (pin "16") (pinfunction "SW1_16") (pintype "passive"))
      (node (ref "U$1") (pin "17") (pinfunction "SW1_17") (pintype "passive"))
      (node (ref "U$2") (pin "2") (pinfunction "2_2") (pintype "passive"))
    )
    (net (code "45") (name "Net-(U$1-SW2-Pad18)") (class "Default")
      (node (ref "U$1") (pin "18") (pinfunction "SW2_18") (pintype "passive"))
      (node (ref "U$1") (pin "19") (pinfunction "SW2_19") (pintype "passive"))
      (node (ref "U$2") (pin "1") (pinfunction "1_1") (pintype "passive"))
    )
    (net (code "46") (name "Net-(U$1-VC)") (class "Default")
      (node (ref "C19") (pin "1") (pinfunction "1_1") (pintype "passive"))
      (node (ref "R6") (pin "2") (pinfunction "2_2") (pintype "passive"))
      (node (ref "U$1") (pin "12") (pinfunction "VC_12") (pintype "passive"))
    )
    (net (code "47") (name "unconnected-(FTDI-Pad2)") (class "Default")
      (node (ref "FTDI") (pin "2") (pinfunction "2_2") (pintype "passive"))
    )
    (net (code "48") (name "unconnected-(FTDI-Pad6)") (class "Default")
      (node (ref "FTDI") (pin "6") (pinfunction "6_6") (pintype "passive"))
    )
    (net (code "49") (name "unconnected-(IC1-BOOTO-Pad138)") (class "Default")
      (node (ref "IC1") (pin "138") (pinfunction "BOOTO_138") (pintype "bidirectional"))
    )
    (net (code "50") (name "unconnected-(IC1-PA1-Pad35)") (class "Default")
      (node (ref "IC1") (pin "35") (pinfunction "PA1_35") (pintype "bidirectional"))
    )
    (net (code "51") (name "unconnected-(IC1-PA2-Pad36)") (class "Default")
      (node (ref "IC1") (pin "36") (pinfunction "PA2_36") (pintype "bidirectional"))
    )
    (net (code "52") (name "unconnected-(IC1-PA3-Pad37)") (class "Default")
      (node (ref "IC1") (pin "37") (pinfunction "PA3_37") (pintype "bidirectional"))
    )
    (net (code "53") (name "unconnected-(IC1-PA4-Pad40)") (class "Default")
      (node (ref "IC1") (pin "40") (pinfunction "PA4_40") (pintype "bidirectional"))
    )
    (net (code "54") (name "unconnected-(IC1-PA5-Pad41)") (class "Default")
      (node (ref "IC1") (pin "41") (pinfunction "PA5_41") (pintype "bidirectional"))
    )
    (net (code "55") (name "unconnected-(IC1-PA6-Pad42)") (class "Default")
      (node (ref "IC1") (pin "42") (pinfunction "PA6_42") (pintype "bidirectional"))
    )
    (net (code "56") (name "unconnected-(IC1-PA7-Pad43)") (class "Default")
      (node (ref "IC1") (pin "43") (pinfunction "PA7_43") (pintype "bidirectional"))
    )
    (net (code "57") (name "unconnected-(IC1-PA8-Pad100)") (class "Default")
      (node (ref "IC1") (pin "100") (pinfunction "PA8_100") (pintype "bidirectional"))
    )
    (net (code "58") (name "unconnected-(IC1-PA11-Pad103)") (class "Default")
      (node (ref "IC1") (pin "103") (pinfunction "PA11_103") (pintype "bidirectional"))
    )
    (net (code "59") (name "unconnected-(IC1-PA12-Pad104)") (class "Default")
      (node (ref "IC1") (pin "104") (pinfunction "PA12_104") (pintype "bidirectional"))
    )
    (net (code "60") (name "unconnected-(IC1-PA15-Pad110)") (class "Default")
      (node (ref "IC1") (pin "110") (pinfunction "PA15_110") (pintype "bidirectional"))
    )
    (net (code "61") (name "unconnected-(IC1-PAO-Pad34)") (class "Default")
      (node (ref "IC1") (pin "34") (pinfunction "PAO_34") (pintype "bidirectional"))
    )
    (net (code "62") (name "unconnected-(IC1-PB4-Pad134)") (class "Default")
      (node (ref "IC1") (pin "134") (pinfunction "PB4_134") (pintype "bidirectional"))
    )
    (net (code "63") (name "unconnected-(IC1-PB5-Pad135)") (class "Default")
      (node (ref "IC1") (pin "135") (pinfunction "PB5_135") (pintype "bidirectional"))
    )
    (net (code "64") (name "unconnected-(IC1-PB6-Pad136)") (class "Default")
      (node (ref "IC1") (pin "136") (pinfunction "PB6_136") (pintype "bidirectional"))
    )
    (net (code "65") (name "unconnected-(IC1-PB7-Pad137)") (class "Default")
      (node (ref "IC1") (pin "137") (pinfunction "PB7_137") (pintype "bidirectional"))
    )
    (net (code "66") (name "unconnected-(IC1-PB8-Pad139)") (class "Default")
      (node (ref "IC1") (pin "139") (pinfunction "PB8_139") (pintype "bidirectional"))
    )
    (net (code "67") (name "unconnected-(IC1-PB9-Pad140)") (class "Default")
      (node (ref "IC1") (pin "140") (pinfunction "PB9_140") (pintype "bidirectional"))
    )
    (net (code "68") (name "unconnected-(IC1-PB10-Pad69)") (class "Default")
      (node (ref "IC1") (pin "69") (pinfunction "PB10_69") (pintype "bidirectional"))
    )
    (net (code "69") (name "unconnected-(IC1-PB11-Pad70)") (class "Default")
      (node (ref "IC1") (pin "70") (pinfunction "PB11_70") (pintype "bidirectional"))
    )
    (net (code "70") (name "unconnected-(IC1-PB12-Pad73)") (class "Default")
      (node (ref "IC1") (pin "73") (pinfunction "PB12_73") (pintype "bidirectional"))
    )
    (net (code "71") (name "unconnected-(IC1-PB13-Pad74)") (class "Default")
      (node (ref "IC1") (pin "74") (pinfunction "PB13_74") (pintype "bidirectional"))
    )
    (net (code "72") (name "unconnected-(IC1-PB14-Pad75)") (class "Default")
      (node (ref "IC1") (pin "75") (pinfunction "PB14_75") (pintype "bidirectional"))
    )
    (net (code "73") (name "unconnected-(IC1-PB15-Pad76)") (class "Default")
      (node (ref "IC1") (pin "76") (pinfunction "PB15_76") (pintype "bidirectional"))
    )
    (net (code "74") (name "unconnected-(IC1-PBO-Pad46)") (class "Default")
      (node (ref "IC1") (pin "46") (pinfunction "PBO_46") (pintype "bidirectional"))
    )
    (net (code "75") (name "unconnected-(IC1-PC1-Pad27)") (class "Default")
      (node (ref "IC1") (pin "27") (pinfunction "PC1_27") (pintype "bidirectional"))
    )
    (net (code "76") (name "unconnected-(IC1-PC2-Pad28)") (class "Default")
      (node (ref "IC1") (pin "28") (pinfunction "PC2_28") (pintype "bidirectional"))
    )
    (net (code "77") (name "unconnected-(IC1-PC3-Pad29)") (class "Default")
      (node (ref "IC1") (pin "29") (pinfunction "PC3_29") (pintype "bidirectional"))
    )
    (net (code "78") (name "unconnected-(IC1-PC4-Pad44)") (class "Default")
      (node (ref "IC1") (pin "44") (pinfunction "PC4_44") (pintype "bidirectional"))
    )
    (net (code "79") (name "unconnected-(IC1-PC5-Pad45)") (class "Default")
      (node (ref "IC1") (pin "45") (pinfunction "PC5_45") (pintype "bidirectional"))
    )
    (net (code "80") (name "unconnected-(IC1-PC6-Pad96)") (class "Default")
      (node (ref "IC1") (pin "96") (pinfunction "PC6_96") (pintype "bidirectional"))
    )
    (net (code "81") (name "unconnected-(IC1-PC7-Pad97)") (class "Default")
      (node (ref "IC1") (pin "97") (pinfunction "PC7_97") (pintype "bidirectional"))
    )
    (net (code "82") (name "unconnected-(IC1-PC8-Pad98)") (class "Default")
      (node (ref "IC1") (pin "98") (pinfunction "PC8_98") (pintype "bidirectional"))
    )
    (net (code "83") (name "unconnected-(IC1-PC9-Pad99)") (class "Default")
      (node (ref "IC1") (pin "99") (pinfunction "PC9_99") (pintype "bidirectional"))
    )
    (net (code "84") (name "unconnected-(IC1-PC10-Pad111)") (class "Default")
      (node (ref "IC1") (pin "111") (pinfunction "PC10_111") (pintype "bidirectional"))
    )
    (net (code "85") (name "unconnected-(IC1-PC13-Pad7)") (class "Default")
      (node (ref "IC1") (pin "7") (pinfunction "PC13_7") (pintype "bidirectional"))
    )
    (net (code "86") (name "unconnected-(IC1-PC14-Pad8)") (class "Default")
      (node (ref "IC1") (pin "8") (pinfunction "PC14_8") (pintype "bidirectional"))
    )
    (net (code "87") (name "unconnected-(IC1-PC15-Pad9)") (class "Default")
      (node (ref "IC1") (pin "9") (pinfunction "PC15_9") (pintype "bidirectional"))
    )
    (net (code "88") (name "unconnected-(IC1-PCO-Pad26)") (class "Default")
      (node (ref "IC1") (pin "26") (pinfunction "PCO_26") (pintype "bidirectional"))
    )
    (net (code "89") (name "unconnected-(IC1-PD1-Pad115)") (class "Default")
      (node (ref "IC1") (pin "115") (pinfunction "PD1_115") (pintype "bidirectional"))
    )
    (net (code "90") (name "unconnected-(IC1-PD3-Pad117)") (class "Default")
      (node (ref "IC1") (pin "117") (pinfunction "PD3_117") (pintype "bidirectional"))
    )
    (net (code "91") (name "unconnected-(IC1-PD4-Pad118)") (class "Default")
      (node (ref "IC1") (pin "118") (pinfunction "PD4_118") (pintype "bidirectional"))
    )
    (net (code "92") (name "unconnected-(IC1-PD5-Pad119)") (class "Default")
      (node (ref "IC1") (pin "119") (pinfunction "PD5_119") (pintype "bidirectional"))
    )
    (net (code "93") (name "unconnected-(IC1-PD6-Pad122)") (class "Default")
      (node (ref "IC1") (pin "122") (pinfunction "PD6_122") (pintype "bidirectional"))
    )
    (net (code "94") (name "unconnected-(IC1-PD7-Pad123)") (class "Default")
      (node (ref "IC1") (pin "123") (pinfunction "PD7_123") (pintype "bidirectional"))
    )
    (net (code "95") (name "unconnected-(IC1-PD8-Pad77)") (class "Default")
      (node (ref "IC1") (pin "77") (pinfunction "PD8_77") (pintype "bidirectional"))
    )
    (net (code "96") (name "unconnected-(IC1-PD9-Pad78)") (class "Default")
      (node (ref "IC1") (pin "78") (pinfunction "PD9_78") (pintype "bidirectional"))
    )
    (net (code "97") (name "unconnected-(IC1-PD10-Pad79)") (class "Default")
      (node (ref "IC1") (pin "79") (pinfunction "PD10_79") (pintype "bidirectional"))
    )
    (net (code "98") (name "unconnected-(IC1-PD11-Pad80)") (class "Default")
      (node (ref "IC1") (pin "80") (pinfunction "PD11_80") (pintype "bidirectional"))
    )
    (net (code "99") (name "unconnected-(IC1-PD12-Pad81)") (class "Default")
      (node (ref "IC1") (pin "81") (pinfunction "PD12_81") (pintype "bidirectional"))
    )
    (net (code "100") (name "unconnected-(IC1-PD13-Pad82)") (class "Default")
      (node (ref "IC1") (pin "82") (pinfunction "PD13_82") (pintype "bidirectional"))
    )
    (net (code "101") (name "unconnected-(IC1-PD14-Pad85)") (class "Default")
      (node (ref "IC1") (pin "85") (pinfunction "PD14_85") (pintype "bidirectional"))
    )
    (net (code "102") (name "unconnected-(IC1-PD15-Pad86)") (class "Default")
      (node (ref "IC1") (pin "86") (pinfunction "PD15_86") (pintype "bidirectional"))
    )
    (net (code "103") (name "unconnected-(IC1-PDO-Pad114)") (class "Default")
      (node (ref "IC1") (pin "114") (pinfunction "PDO_114") (pintype "bidirectional"))
    )
    (net (code "104") (name "unconnected-(IC1-PDR_ON-Pad143)") (class "Default")
      (node (ref "IC1") (pin "143") (pinfunction "PDR_ON_143") (pintype "bidirectional"))
    )
    (net (code "105") (name "unconnected-(IC1-PE1-Pad142)") (class "Default")
      (node (ref "IC1") (pin "142") (pinfunction "PE1_142") (pintype "bidirectional"))
    )
    (net (code "106") (name "unconnected-(IC1-PE5-Pad4)") (class "Default")
      (node (ref "IC1") (pin "4") (pinfunction "PE5_4") (pintype "bidirectional"))
    )
    (net (code "107") (name "unconnected-(IC1-PE11-Pad64)") (class "Default")
      (node (ref "IC1") (pin "64") (pinfunction "PE11_64") (pintype "bidirectional"))
    )
    (net (code "108") (name "unconnected-(IC1-PE12-Pad65)") (class "Default")
      (node (ref "IC1") (pin "65") (pinfunction "PE12_65") (pintype "bidirectional"))
    )
    (net (code "109") (name "unconnected-(IC1-PE13-Pad66)") (class "Default")
      (node (ref "IC1") (pin "66") (pinfunction "PE13_66") (pintype "bidirectional"))
    )
    (net (code "110") (name "unconnected-(IC1-PE14-Pad67)") (class "Default")
      (node (ref "IC1") (pin "67") (pinfunction "PE14_67") (pintype "bidirectional"))
    )
    (net (code "111") (name "unconnected-(IC1-PE15-Pad68)") (class "Default")
      (node (ref "IC1") (pin "68") (pinfunction "PE15_68") (pintype "bidirectional"))
    )
    (net (code "112") (name "unconnected-(IC1-PEO-Pad141)") (class "Default")
      (node (ref "IC1") (pin "141") (pinfunction "PEO_141") (pintype "bidirectional"))
    )
    (net (code "113") (name "unconnected-(IC1-PF1-Pad11)") (class "Default")
      (node (ref "IC1") (pin "11") (pinfunction "PF1_11") (pintype "bidirectional"))
    )
    (net (code "114") (name "unconnected-(IC1-PF2-Pad12)") (class "Default")
      (node (ref "IC1") (pin "12") (pinfunction "PF2_12") (pintype "bidirectional"))
    )
    (net (code "115") (name "unconnected-(IC1-PF3-Pad13)") (class "Default")
      (node (ref "IC1") (pin "13") (pinfunction "PF3_13") (pintype "bidirectional"))
    )
    (net (code "116") (name "unconnected-(IC1-PF4-Pad14)") (class "Default")
      (node (ref "IC1") (pin "14") (pinfunction "PF4_14") (pintype "bidirectional"))
    )
    (net (code "117") (name "unconnected-(IC1-PF5-Pad15)") (class "Default")
      (node (ref "IC1") (pin "15") (pinfunction "PF5_15") (pintype "bidirectional"))
    )
    (net (code "118") (name "unconnected-(IC1-PF7-Pad19)") (class "Default")
      (node (ref "IC1") (pin "19") (pinfunction "PF7_19") (pintype "bidirectional"))
    )
    (net (code "119") (name "unconnected-(IC1-PF8-Pad20)") (class "Default")
      (node (ref "IC1") (pin "20") (pinfunction "PF8_20") (pintype "bidirectional"))
    )
    (net (code "120") (name "unconnected-(IC1-PF9-Pad21)") (class "Default")
      (node (ref "IC1") (pin "21") (pinfunction "PF9_21") (pintype "bidirectional"))
    )
    (net (code "121") (name "unconnected-(IC1-PF10-Pad22)") (class "Default")
      (node (ref "IC1") (pin "22") (pinfunction "PF10_22") (pintype "bidirectional"))
    )
    (net (code "122") (name "unconnected-(IC1-PF11-Pad49)") (class "Default")
      (node (ref "IC1") (pin "49") (pinfunction "PF11_49") (pintype "bidirectional"))
    )
    (net (code "123") (name "unconnected-(IC1-PF12-Pad50)") (class "Default")
      (node (ref "IC1") (pin "50") (pinfunction "PF12_50") (pintype "bidirectional"))
    )
    (net (code "124") (name "unconnected-(IC1-PF13-Pad53)") (class "Default")
      (node (ref "IC1") (pin "53") (pinfunction "PF13_53") (pintype "bidirectional"))
    )
    (net (code "125") (name "unconnected-(IC1-PF14-Pad54)") (class "Default")
      (node (ref "IC1") (pin "54") (pinfunction "PF14_54") (pintype "bidirectional"))
    )
    (net (code "126") (name "unconnected-(IC1-PF15-Pad55)") (class "Default")
      (node (ref "IC1") (pin "55") (pinfunction "PF15_55") (pintype "bidirectional"))
    )
    (net (code "127") (name "unconnected-(IC1-PFO-Pad10)") (class "Default")
      (node (ref "IC1") (pin "10") (pinfunction "PFO_10") (pintype "bidirectional"))
    )
    (net (code "128") (name "unconnected-(IC1-PG1-Pad57)") (class "Default")
      (node (ref "IC1") (pin "57") (pinfunction "PG1_57") (pintype "bidirectional"))
    )
    (net (code "129") (name "unconnected-(IC1-PG2-Pad87)") (class "Default")
      (node (ref "IC1") (pin "87") (pinfunction "PG2_87") (pintype "bidirectional"))
    )
    (net (code "130") (name "unconnected-(IC1-PG3-Pad88)") (class "Default")
      (node (ref "IC1") (pin "88") (pinfunction "PG3_88") (pintype "bidirectional"))
    )
    (net (code "131") (name "unconnected-(IC1-PG4-Pad89)") (class "Default")
      (node (ref "IC1") (pin "89") (pinfunction "PG4_89") (pintype "bidirectional"))
    )
    (net (code "132") (name "unconnected-(IC1-PG5-Pad90)") (class "Default")
      (node (ref "IC1") (pin "90") (pinfunction "PG5_90") (pintype "bidirectional"))
    )
    (net (code "133") (name "unconnected-(IC1-PG6-Pad91)") (class "Default")
      (node (ref "IC1") (pin "91") (pinfunction "PG6_91") (pintype "bidirectional"))
    )
    (net (code "134") (name "unconnected-(IC1-PG7-Pad92)") (class "Default")
      (node (ref "IC1") (pin "92") (pinfunction "PG7_92") (pintype "bidirectional"))
    )
    (net (code "135") (name "unconnected-(IC1-PG8-Pad93)") (class "Default")
      (node (ref "IC1") (pin "93") (pinfunction "PG8_93") (pintype "bidirectional"))
    )
    (net (code "136") (name "unconnected-(IC1-PG9-Pad124)") (class "Default")
      (node (ref "IC1") (pin "124") (pinfunction "PG9_124") (pintype "bidirectional"))
    )
    (net (code "137") (name "unconnected-(IC1-PG10-Pad125)") (class "Default")
      (node (ref "IC1") (pin "125") (pinfunction "PG10_125") (pintype "bidirectional"))
    )
    (net (code "138") (name "unconnected-(IC1-PG11-Pad126)") (class "Default")
      (node (ref "IC1") (pin "126") (pinfunction "PG11_126") (pintype "bidirectional"))
    )
    (net (code "139") (name "unconnected-(IC1-PG12-Pad127)") (class "Default")
      (node (ref "IC1") (pin "127") (pinfunction "PG12_127") (pintype "bidirectional"))
    )
    (net (code "140") (name "unconnected-(IC1-PG13-Pad128)") (class "Default")
      (node (ref "IC1") (pin "128") (pinfunction "PG13_128") (pintype "bidirectional"))
    )
    (net (code "141") (name "unconnected-(IC1-PG14-Pad129)") (class "Default")
      (node (ref "IC1") (pin "129") (pinfunction "PG14_129") (pintype "bidirectional"))
    )
    (net (code "142") (name "unconnected-(IC1-PG15-Pad132)") (class "Default")
      (node (ref "IC1") (pin "132") (pinfunction "PG15_132") (pintype "bidirectional"))
    )
    (net (code "143") (name "unconnected-(IC1-PGO-Pad56)") (class "Default")
      (node (ref "IC1") (pin "56") (pinfunction "PGO_56") (pintype "bidirectional"))
    )
    (net (code "144") (name "unconnected-(IC1-VBAT-Pad6)") (class "Default")
      (node (ref "IC1") (pin "6") (pinfunction "VBAT_6") (pintype "bidirectional"))
    )
    (net (code "145") (name "unconnected-(J2-NC{slash}TDI-Pad8)") (class "Default")
      (node (ref "J2") (pin "8") (pinfunction "NC/TDI_8") (pintype "bidirectional"))
    )
    (net (code "146") (name "unconnected-(LCDCONNECTORB-KL-Pad10)") (class "Default")
      (node (ref "LCDCONNECTOR") (pin "10") (pinfunction "KL_10") (pintype "passive"))
    )
    (net (code "147") (name "unconnected-(LCDCONNECTORE-KL-Pad13)") (class "Default")
      (node (ref "LCDCONNECTOR") (pin "13") (pinfunction "KL_13") (pintype "passive"))
    )
    (net (code "148") (name "unconnected-(LCDCONNECTORF-KL-Pad14)") (class "Default")
      (node (ref "LCDCONNECTOR") (pin "14") (pinfunction "KL_14") (pintype "passive"))
    )
    (net (code "149") (name "unconnected-(LCDCONNECTORG-KL-Pad15)") (class "Default")
      (node (ref "LCDCONNECTOR") (pin "15") (pinfunction "KL_15") (pintype "passive"))
    )
    (net (code "150") (name "unconnected-(LCDCONNECTORH-KL-Pad16)") (class "Default")
      (node (ref "LCDCONNECTOR") (pin "16") (pinfunction "KL_16") (pintype "passive"))
    )
    (net (code "151") (name "unconnected-(LCDCONNECTORR-KL-Pad7)") (class "Default")
      (node (ref "LCDCONNECTOR") (pin "7") (pinfunction "KL_7") (pintype "passive"))
    )
    (net (code "152") (name "unconnected-(LCDCONNECTORT-KL-Pad9)") (class "Default")
      (node (ref "LCDCONNECTOR") (pin "9") (pinfunction "KL_9") (pintype "passive"))
    )
    (net (code "153") (name "unconnected-(P1-Pad2)") (class "Default")
      (node (ref "P1") (pin "2") (pinfunction "2_2") (pintype "passive"))
    )
    (net (code "154") (name "unconnected-(P1-Pad3)") (class "Default")
      (node (ref "P1") (pin "3") (pinfunction "3_3") (pintype "passive"))
    )
    (net (code "155") (name "unconnected-(P1-Pad4)") (class "Default")
      (node (ref "P1") (pin "4") (pinfunction "4_4") (pintype "passive"))
    )
    (net (code "156") (name "unconnected-(P1-Pad5)") (class "Default")
      (node (ref "P1") (pin "5") (pinfunction "5_5") (pintype "passive"))
    )
    (net (code "157") (name "unconnected-(P1-Pad6)") (class "Default")
      (node (ref "P1") (pin "6") (pinfunction "6_6") (pintype "passive"))
    )
    (net (code "158") (name "unconnected-(P1-Pad9)") (class "Default")
      (node (ref "P1") (pin "9") (pinfunction "9_9") (pintype "passive"))
    )
    (net (code "159") (name "unconnected-(P1-Pad10)") (class "Default")
      (node (ref "P1") (pin "10") (pinfunction "10_10") (pintype "passive"))
    )
    (net (code "160") (name "unconnected-(P1-Pad11)") (class "Default")
      (node (ref "P1") (pin "11") (pinfunction "11_11") (pintype "passive"))
    )
    (net (code "161") (name "unconnected-(P1-Pad12)") (class "Default")
      (node (ref "P1") (pin "12") (pinfunction "12_12") (pintype "passive"))
    )
    (net (code "162") (name "unconnected-(P1-Pad15)") (class "Default")
      (node (ref "P1") (pin "15") (pinfunction "15_15") (pintype "passive"))
    )
    (net (code "163") (name "unconnected-(P1-Pad16)") (class "Default")
      (node (ref "P1") (pin "16") (pinfunction "16_16") (pintype "passive"))
    )
    (net (code "164") (name "unconnected-(P1-Pad17)") (class "Default")
      (node (ref "P1") (pin "17") (pinfunction "17_17") (pintype "passive"))
    )
    (net (code "165") (name "unconnected-(P1-Pad18)") (class "Default")
      (node (ref "P1") (pin "18") (pinfunction "18_18") (pintype "passive"))
    )
    (net (code "166") (name "unconnected-(P1-Pad21)") (class "Default")
      (node (ref "P1") (pin "21") (pinfunction "21_21") (pintype "passive"))
    )
    (net (code "167") (name "unconnected-(P1-Pad22)") (class "Default")
      (node (ref "P1") (pin "22") (pinfunction "22_22") (pintype "passive"))
    )
    (net (code "168") (name "unconnected-(P1-Pad23)") (class "Default")
      (node (ref "P1") (pin "23") (pinfunction "23_23") (pintype "passive"))
    )
    (net (code "169") (name "unconnected-(P1-Pad24)") (class "Default")
      (node (ref "P1") (pin "24") (pinfunction "24_24") (pintype "passive"))
    )
    (net (code "170") (name "unconnected-(P1-Pad27)") (class "Default")
      (node (ref "P1") (pin "27") (pinfunction "27_27") (pintype "passive"))
    )
    (net (code "171") (name "unconnected-(P1-Pad28)") (class "Default")
      (node (ref "P1") (pin "28") (pinfunction "28_28") (pintype "passive"))
    )
    (net (code "172") (name "unconnected-(P1-Pad29)") (class "Default")
      (node (ref "P1") (pin "29") (pinfunction "29_29") (pintype "passive"))
    )
    (net (code "173") (name "unconnected-(P1-Pad30)") (class "Default")
      (node (ref "P1") (pin "30") (pinfunction "30_30") (pintype "passive"))
    )
    (net (code "174") (name "unconnected-(P1-Pad33)") (class "Default")
      (node (ref "P1") (pin "33") (pinfunction "33_33") (pintype "passive"))
    )
    (net (code "175") (name "unconnected-(P1-Pad34)") (class "Default")
      (node (ref "P1") (pin "34") (pinfunction "34_34") (pintype "passive"))
    )
    (net (code "176") (name "unconnected-(P1-Pad35)") (class "Default")
      (node (ref "P1") (pin "35") (pinfunction "35_35") (pintype "passive"))
    )
    (net (code "177") (name "unconnected-(P1-Pad36)") (class "Default")
      (node (ref "P1") (pin "36") (pinfunction "36_36") (pintype "passive"))
    )
    (net (code "178") (name "unconnected-(P1-Pad39)") (class "Default")
      (node (ref "P1") (pin "39") (pinfunction "39_39") (pintype "passive"))
    )
    (net (code "179") (name "unconnected-(P1-Pad40)") (class "Default")
      (node (ref "P1") (pin "40") (pinfunction "40_40") (pintype "passive"))
    )
    (net (code "180") (name "unconnected-(P1-Pad41)") (class "Default")
      (node (ref "P1") (pin "41") (pinfunction "41_41") (pintype "passive"))
    )
    (net (code "181") (name "unconnected-(P1-Pad42)") (class "Default")
      (node (ref "P1") (pin "42") (pinfunction "42_42") (pintype "passive"))
    )
    (net (code "182") (name "unconnected-(P1-Pad45)") (class "Default")
      (node (ref "P1") (pin "45") (pinfunction "45_45") (pintype "passive"))
    )
    (net (code "183") (name "unconnected-(P1-Pad46)") (class "Default")
      (node (ref "P1") (pin "46") (pinfunction "46_46") (pintype "passive"))
    )
    (net (code "184") (name "unconnected-(P1-Pad47)") (class "Default")
      (node (ref "P1") (pin "47") (pinfunction "47_47") (pintype "passive"))
    )
    (net (code "185") (name "unconnected-(P1-Pad48)") (class "Default")
      (node (ref "P1") (pin "48") (pinfunction "48_48") (pintype "passive"))
    )
    (net (code "186") (name "unconnected-(P1-Pad52)") (class "Default")
      (node (ref "P1") (pin "52") (pinfunction "52_52") (pintype "passive"))
    )
    (net (code "187") (name "unconnected-(P1-Pad54)") (class "Default")
      (node (ref "P1") (pin "54") (pinfunction "54_54") (pintype "passive"))
    )
    (net (code "188") (name "unconnected-(P1-Pad57)") (class "Default")
      (node (ref "P1") (pin "57") (pinfunction "57_57") (pintype "passive"))
    )
    (net (code "189") (name "unconnected-(P1-Pad58)") (class "Default")
      (node (ref "P1") (pin "58") (pinfunction "58_58") (pintype "passive"))
    )
    (net (code "190") (name "unconnected-(P1-Pad59)") (class "Default")
      (node (ref "P1") (pin "59") (pinfunction "59_59") (pintype "passive"))
    )
    (net (code "191") (name "unconnected-(P1-Pad60)") (class "Default")
      (node (ref "P1") (pin "60") (pinfunction "60_60") (pintype "passive"))
    )
    (net (code "192") (name "unconnected-(P1-Pad63)") (class "Default")
      (node (ref "P1") (pin "63") (pinfunction "63_63") (pintype "passive"))
    )
    (net (code "193") (name "unconnected-(P1-Pad64)") (class "Default")
      (node (ref "P1") (pin "64") (pinfunction "64_64") (pintype "passive"))
    )
    (net (code "194") (name "unconnected-(P1-Pad65)") (class "Default")
      (node (ref "P1") (pin "65") (pinfunction "65_65") (pintype "passive"))
    )
    (net (code "195") (name "unconnected-(P1-Pad66)") (class "Default")
      (node (ref "P1") (pin "66") (pinfunction "66_66") (pintype "passive"))
    )
    (net (code "196") (name "unconnected-(P1-Pad69)") (class "Default")
      (node (ref "P1") (pin "69") (pinfunction "69_69") (pintype "passive"))
    )
    (net (code "197") (name "unconnected-(P1-Pad70)") (class "Default")
      (node (ref "P1") (pin "70") (pinfunction "70_70") (pintype "passive"))
    )
    (net (code "198") (name "unconnected-(P1-Pad71)") (class "Default")
      (node (ref "P1") (pin "71") (pinfunction "71_71") (pintype "passive"))
    )
    (net (code "199") (name "unconnected-(P1-Pad72)") (class "Default")
      (node (ref "P1") (pin "72") (pinfunction "72_72") (pintype "passive"))
    )
    (net (code "200") (name "unconnected-(P1-Pad75)") (class "Default")
      (node (ref "P1") (pin "75") (pinfunction "75_75") (pintype "passive"))
    )
    (net (code "201") (name "unconnected-(P1-Pad76)") (class "Default")
      (node (ref "P1") (pin "76") (pinfunction "76_76") (pintype "passive"))
    )
    (net (code "202") (name "unconnected-(P1-Pad77)") (class "Default")
      (node (ref "P1") (pin "77") (pinfunction "77_77") (pintype "passive"))
    )
    (net (code "203") (name "unconnected-(P1-Pad78)") (class "Default")
      (node (ref "P1") (pin "78") (pinfunction "78_78") (pintype "passive"))
    )
    (net (code "204") (name "unconnected-(P1-Pad81)") (class "Default")
      (node (ref "P1") (pin "81") (pinfunction "81_81") (pintype "passive"))
    )
    (net (code "205") (name "unconnected-(P1-Pad82)") (class "Default")
      (node (ref "P1") (pin "82") (pinfunction "82_82") (pintype "passive"))
    )
    (net (code "206") (name "unconnected-(P1-Pad83)") (class "Default")
      (node (ref "P1") (pin "83") (pinfunction "83_83") (pintype "passive"))
    )
    (net (code "207") (name "unconnected-(P1-Pad84)") (class "Default")
      (node (ref "P1") (pin "84") (pinfunction "84_84") (pintype "passive"))
    )
    (net (code "208") (name "unconnected-(P1-Pad87)") (class "Default")
      (node (ref "P1") (pin "87") (pinfunction "87_87") (pintype "passive"))
    )
    (net (code "209") (name "unconnected-(P1-Pad88)") (class "Default")
      (node (ref "P1") (pin "88") (pinfunction "88_88") (pintype "passive"))
    )
    (net (code "210") (name "unconnected-(P1-Pad89)") (class "Default")
      (node (ref "P1") (pin "89") (pinfunction "89_89") (pintype "passive"))
    )
    (net (code "211") (name "unconnected-(P1-Pad90)") (class "Default")
      (node (ref "P1") (pin "90") (pinfunction "90_90") (pintype "passive"))
    )
    (net (code "212") (name "unconnected-(P1-Pad93)") (class "Default")
      (node (ref "P1") (pin "93") (pinfunction "93_93") (pintype "passive"))
    )
    (net (code "213") (name "unconnected-(P1-Pad94)") (class "Default")
      (node (ref "P1") (pin "94") (pinfunction "94_94") (pintype "passive"))
    )
    (net (code "214") (name "unconnected-(P1-Pad95)") (class "Default")
      (node (ref "P1") (pin "95") (pinfunction "95_95") (pintype "passive"))
    )
    (net (code "215") (name "unconnected-(P1-Pad96)") (class "Default")
      (node (ref "P1") (pin "96") (pinfunction "96_96") (pintype "passive"))
    )
    (net (code "216") (name "unconnected-(P1-Pad99)") (class "Default")
      (node (ref "P1") (pin "99") (pinfunction "99_99") (pintype "passive"))
    )
    (net (code "217") (name "unconnected-(P1-Pad100)") (class "Default")
      (node (ref "P1") (pin "100") (pinfunction "100_100") (pintype "passive"))
    )
    (net (code "218") (name "unconnected-(P1-Pad101)") (class "Default")
      (node (ref "P1") (pin "101") (pinfunction "101_101") (pintype "passive"))
    )
    (net (code "219") (name "unconnected-(P1-Pad102)") (class "Default")
      (node (ref "P1") (pin "102") (pinfunction "102_102") (pintype "passive"))
    )
    (net (code "220") (name "unconnected-(P1-Pad105)") (class "Default")
      (node (ref "P1") (pin "105") (pinfunction "105_105") (pintype "passive"))
    )
    (net (code "221") (name "unconnected-(P1-Pad106)") (class "Default")
      (node (ref "P1") (pin "106") (pinfunction "106_106") (pintype "passive"))
    )
    (net (code "222") (name "unconnected-(P1-Pad107)") (class "Default")
      (node (ref "P1") (pin "107") (pinfunction "107_107") (pintype "passive"))
    )
    (net (code "223") (name "unconnected-(P1-Pad108)") (class "Default")
      (node (ref "P1") (pin "108") (pinfunction "108_108") (pintype "passive"))
    )
    (net (code "224") (name "unconnected-(P1-Pad111)") (class "Default")
      (node (ref "P1") (pin "111") (pinfunction "111_111") (pintype "passive"))
    )
    (net (code "225") (name "unconnected-(P1-Pad112)") (class "Default")
      (node (ref "P1") (pin "112") (pinfunction "112_112") (pintype "passive"))
    )
    (net (code "226") (name "unconnected-(P1-Pad113)") (class "Default")
      (node (ref "P1") (pin "113") (pinfunction "113_113") (pintype "passive"))
    )
    (net (code "227") (name "unconnected-(P1-Pad114)") (class "Default")
      (node (ref "P1") (pin "114") (pinfunction "114_114") (pintype "passive"))
    )
    (net (code "228") (name "unconnected-(P1-Pad117)") (class "Default")
      (node (ref "P1") (pin "117") (pinfunction "117_117") (pintype "passive"))
    )
    (net (code "229") (name "unconnected-(P1-Pad118)") (class "Default")
      (node (ref "P1") (pin "118") (pinfunction "118_118") (pintype "passive"))
    )
    (net (code "230") (name "unconnected-(P1-Pad119)") (class "Default")
      (node (ref "P1") (pin "119") (pinfunction "119_119") (pintype "passive"))
    )
    (net (code "231") (name "unconnected-(P1-Pad120)") (class "Default")
      (node (ref "P1") (pin "120") (pinfunction "120_120") (pintype "passive"))
    )
    (net (code "232") (name "unconnected-(P1-Pad123)") (class "Default")
      (node (ref "P1") (pin "123") (pinfunction "123_123") (pintype "passive"))
    )
    (net (code "233") (name "unconnected-(P1-Pad124)") (class "Default")
      (node (ref "P1") (pin "124") (pinfunction "124_124") (pintype "passive"))
    )
    (net (code "234") (name "unconnected-(P1-Pad125)") (class "Default")
      (node (ref "P1") (pin "125") (pinfunction "125_125") (pintype "passive"))
    )
    (net (code "235") (name "unconnected-(P1-Pad126)") (class "Default")
      (node (ref "P1") (pin "126") (pinfunction "126_126") (pintype "passive"))
    )
    (net (code "236") (name "unconnected-(P1-Pad128)") (class "Default")
      (node (ref "P1") (pin "128") (pinfunction "128_128") (pintype "passive"))
    )
    (net (code "237") (name "unconnected-(P1-Pad129)") (class "Default")
      (node (ref "P1") (pin "129") (pinfunction "129_129") (pintype "passive"))
    )
    (net (code "238") (name "unconnected-(P1-Pad130)") (class "Default")
      (node (ref "P1") (pin "130") (pinfunction "130_130") (pintype "passive"))
    )
    (net (code "239") (name "unconnected-(P1-Pad131)") (class "Default")
      (node (ref "P1") (pin "131") (pinfunction "131_131") (pintype "passive"))
    )
    (net (code "240") (name "unconnected-(P1-Pad132)") (class "Default")
      (node (ref "P1") (pin "132") (pinfunction "132_132") (pintype "passive"))
    )
    (net (code "241") (name "unconnected-(P1-Pad135)") (class "Default")
      (node (ref "P1") (pin "135") (pinfunction "135_135") (pintype "passive"))
    )
    (net (code "242") (name "unconnected-(P1-Pad136)") (class "Default")
      (node (ref "P1") (pin "136") (pinfunction "136_136") (pintype "passive"))
    )
    (net (code "243") (name "unconnected-(P1-Pad137)") (class "Default")
      (node (ref "P1") (pin "137") (pinfunction "137_137") (pintype "passive"))
    )
    (net (code "244") (name "unconnected-(P1-Pad138)") (class "Default")
      (node (ref "P1") (pin "138") (pinfunction "138_138") (pintype "passive"))
    )
    (net (code "245") (name "unconnected-(P1-Pad141)") (class "Default")
      (node (ref "P1") (pin "141") (pinfunction "141_141") (pintype "passive"))
    )
    (net (code "246") (name "unconnected-(P1-Pad142)") (class "Default")
      (node (ref "P1") (pin "142") (pinfunction "142_142") (pintype "passive"))
    )
    (net (code "247") (name "unconnected-(P1-Pad143)") (class "Default")
      (node (ref "P1") (pin "143") (pinfunction "143_143") (pintype "passive"))
    )
    (net (code "248") (name "unconnected-(P1-Pad144)") (class "Default")
      (node (ref "P1") (pin "144") (pinfunction "144_144") (pintype "passive"))
    )
    (net (code "249") (name "unconnected-(P1-Pad147)") (class "Default")
      (node (ref "P1") (pin "147") (pinfunction "147_147") (pintype "passive"))
    )
    (net (code "250") (name "unconnected-(P1-Pad148)") (class "Default")
      (node (ref "P1") (pin "148") (pinfunction "148_148") (pintype "passive"))
    )
    (net (code "251") (name "unconnected-(P1-Pad149)") (class "Default")
      (node (ref "P1") (pin "149") (pinfunction "149_149") (pintype "passive"))
    )
    (net (code "252") (name "unconnected-(P1-Pad150)") (class "Default")
      (node (ref "P1") (pin "150") (pinfunction "150_150") (pintype "passive"))
    )
    (net (code "253") (name "unconnected-(P1-Pad153)") (class "Default")
      (node (ref "P1") (pin "153") (pinfunction "153_153") (pintype "passive"))
    )
    (net (code "254") (name "unconnected-(P1-Pad154)") (class "Default")
      (node (ref "P1") (pin "154") (pinfunction "154_154") (pintype "passive"))
    )
    (net (code "255") (name "unconnected-(P1-Pad155)") (class "Default")
      (node (ref "P1") (pin "155") (pinfunction "155_155") (pintype "passive"))
    )
    (net (code "256") (name "unconnected-(P1-Pad156)") (class "Default")
      (node (ref "P1") (pin "156") (pinfunction "156_156") (pintype "passive"))
    )
    (net (code "257") (name "unconnected-(P1-Pad158)") (class "Default")
      (node (ref "P1") (pin "158") (pinfunction "158_158") (pintype "passive"))
    )
    (net (code "258") (name "unconnected-(P1-Pad159)") (class "Default")
      (node (ref "P1") (pin "159") (pinfunction "159_159") (pintype "passive"))
    )
    (net (code "259") (name "unconnected-(P1-Pad160)") (class "Default")
      (node (ref "P1") (pin "160") (pinfunction "160_160") (pintype "passive"))
    )
    (net (code "260") (name "unconnected-(P1-Pad161)") (class "Default")
      (node (ref "P1") (pin "161") (pinfunction "161_161") (pintype "passive"))
    )
    (net (code "261") (name "unconnected-(P1-Pad162)") (class "Default")
      (node (ref "P1") (pin "162") (pinfunction "162_162") (pintype "passive"))
    )
    (net (code "262") (name "unconnected-(P1-Pad166)") (class "Default")
      (node (ref "P1") (pin "166") (pinfunction "166_166") (pintype "passive"))
    )
    (net (code "263") (name "unconnected-(P1-Pad171)") (class "Default")
      (node (ref "P1") (pin "171") (pinfunction "171_171") (pintype "passive"))
    )
    (net (code "264") (name "unconnected-(P1-Pad172)") (class "Default")
      (node (ref "P1") (pin "172") (pinfunction "172_172") (pintype "passive"))
    )
    (net (code "265") (name "unconnected-(P1-Pad173)") (class "Default")
      (node (ref "P1") (pin "173") (pinfunction "173_173") (pintype "passive"))
    )
    (net (code "266") (name "unconnected-(P1-Pad174)") (class "Default")
      (node (ref "P1") (pin "174") (pinfunction "174_174") (pintype "passive"))
    )
    (net (code "267") (name "unconnected-(P1-Pad175)") (class "Default")
      (node (ref "P1") (pin "175") (pinfunction "175_175") (pintype "passive"))
    )
    (net (code "268") (name "unconnected-(P1-Pad176)") (class "Default")
      (node (ref "P1") (pin "176") (pinfunction "176_176") (pintype "passive"))
    )
    (net (code "269") (name "unconnected-(P1-Pad178)") (class "Default")
      (node (ref "P1") (pin "178") (pinfunction "178_178") (pintype "passive"))
    )
    (net (code "270") (name "unconnected-(P1-Pad179)") (class "Default")
      (node (ref "P1") (pin "179") (pinfunction "179_179") (pintype "passive"))
    )
    (net (code "271") (name "unconnected-(P1-Pad180)") (class "Default")
      (node (ref "P1") (pin "180") (pinfunction "180_180") (pintype "passive"))
    )
    (net (code "272") (name "unconnected-(P1-Pad189)") (class "Default")
      (node (ref "P1") (pin "189") (pinfunction "189_189") (pintype "passive"))
    )
    (net (code "273") (name "unconnected-(P1-Pad190)") (class "Default")
      (node (ref "P1") (pin "190") (pinfunction "190_190") (pintype "passive"))
    )
    (net (code "274") (name "unconnected-(PROXIMITYSENSOR-Pad4)") (class "Default")
      (node (ref "PROXIMITYSENSOR") (pin "4") (pinfunction "4_4") (pintype "passive"))
    )
    (net (code "275") (name "unconnected-(U1B-NC-Pad19)") (class "Default")
      (node (ref "U1") (pin "19") (pinfunction "NC_19") (pintype "passive"))
    )
    (net (code "276") (name "unconnected-(U1B-NC_2-Pad1)") (class "Default")
      (node (ref "U1") (pin "1") (pinfunction "NC_2_1") (pintype "passive"))
    )
    (net (code "277") (name "unconnected-(U1B-NC_3-Pad2)") (class "Default")
      (node (ref "U1") (pin "2") (pinfunction "NC_3_2") (pintype "passive"))
    )
    (net (code "278") (name "unconnected-(U1B-NC_4-Pad3)") (class "Default")
      (node (ref "U1") (pin "3") (pinfunction "NC_4_3") (pintype "passive"))
    )
    (net (code "279") (name "unconnected-(U1B-NC_5-Pad5)") (class "Default")
      (node (ref "U1") (pin "5") (pinfunction "NC_5_5") (pintype "passive"))
    )
    (net (code "280") (name "unconnected-(U1B-NC_6-Pad7)") (class "Default")
      (node (ref "U1") (pin "7") (pinfunction "NC_6_7") (pintype "passive"))
    )
    (net (code "281") (name "unconnected-(U1B-NC_7-Pad9)") (class "Default")
      (node (ref "U1") (pin "9") (pinfunction "NC_7_9") (pintype "passive"))
    )
    (net (code "282") (name "unconnected-(U1B-NC_8-Pad10)") (class "Default")
      (node (ref "U1") (pin "10") (pinfunction "NC_8_10") (pintype "passive"))
    )
    (net (code "283") (name "unconnected-(U1B-NC_9-Pad11)") (class "Default")
      (node (ref "U1") (pin "11") (pinfunction "NC_9_11") (pintype "passive"))
    )
    (net (code "284") (name "unconnected-(U1B-NC_10-Pad12)") (class "Default")
      (node (ref "U1") (pin "12") (pinfunction "NC_10_12") (pintype "passive"))
    )
    (net (code "285") (name "unconnected-(U1B-NC_11-Pad13)") (class "Default")
      (node (ref "U1") (pin "13") (pinfunction "NC_11_13") (pintype "passive"))
    )
    (net (code "286") (name "unconnected-(U1B-NC_12-Pad14)") (class "Default")
      (node (ref "U1") (pin "14") (pinfunction "NC_12_14") (pintype "passive"))
    )
    (net (code "287") (name "unconnected-(U1B-NC_13-Pad15)") (class "Default")
      (node (ref "U1") (pin "15") (pinfunction "NC_13_15") (pintype "passive"))
    )
    (net (code "288") (name "unconnected-(U1B-NC_14-Pad16)") (class "Default")
      (node (ref "U1") (pin "16") (pinfunction "NC_14_16") (pintype "passive"))
    )
    (net (code "289") (name "unconnected-(U1B-NC_15-Pad17)") (class "Default")
      (node (ref "U1") (pin "17") (pinfunction "NC_15_17") (pintype "passive"))
    )
    (net (code "290") (name "unconnected-(U1B-NC_16-Pad18)") (class "Default")
      (node (ref "U1") (pin "18") (pinfunction "NC_16_18") (pintype "passive"))
    )
  )
)
